# CFT-PB1-revG-TSSOP.net
KiCad netlist of a schematic drawn in EAGLE
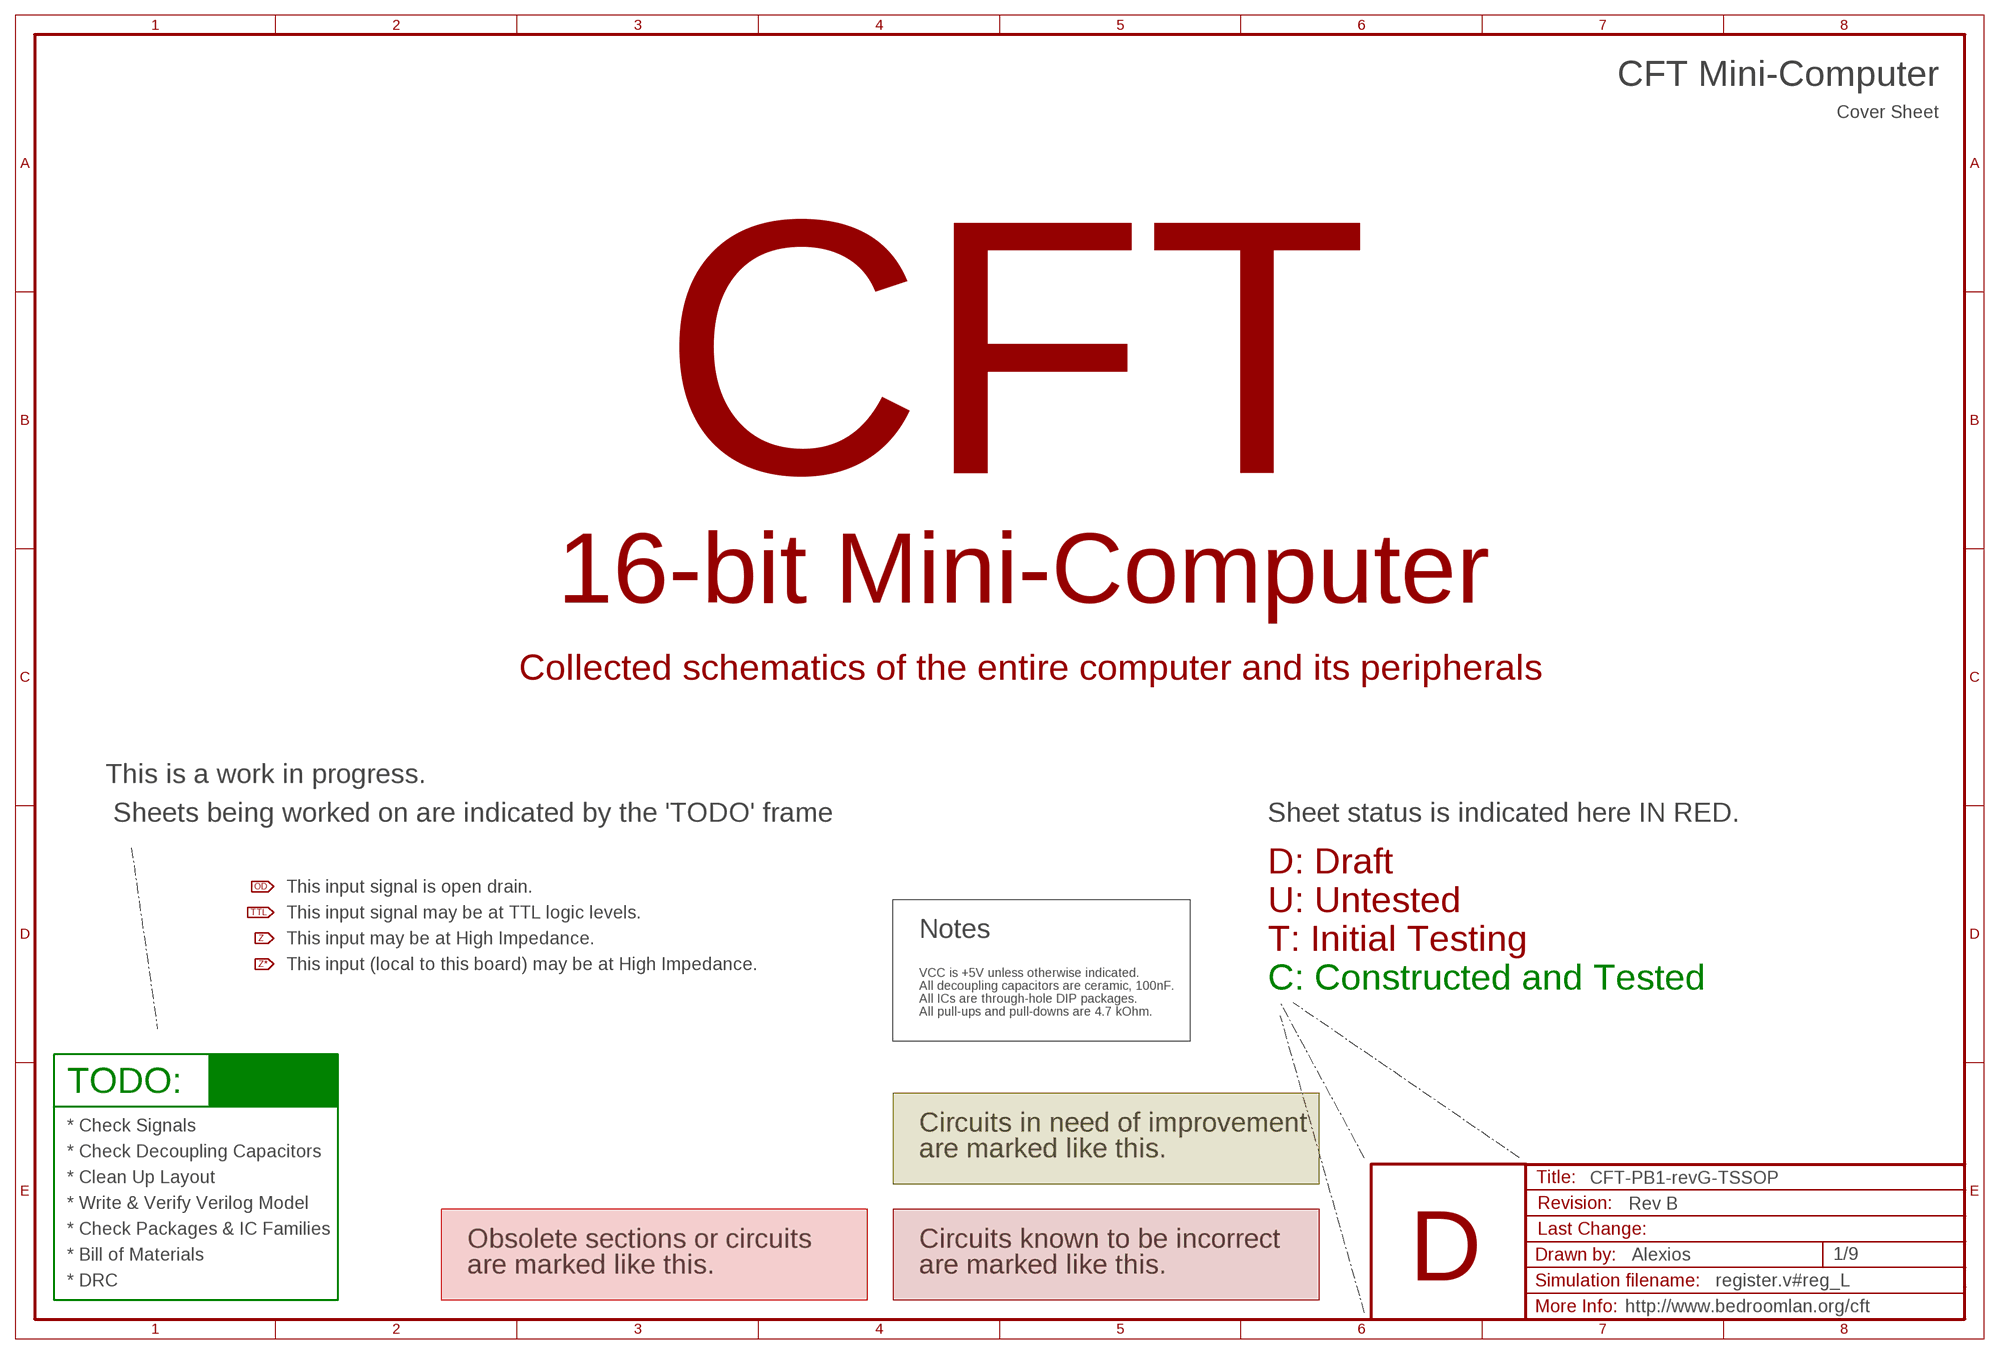
[diagram p0: schematic, sheet 1]
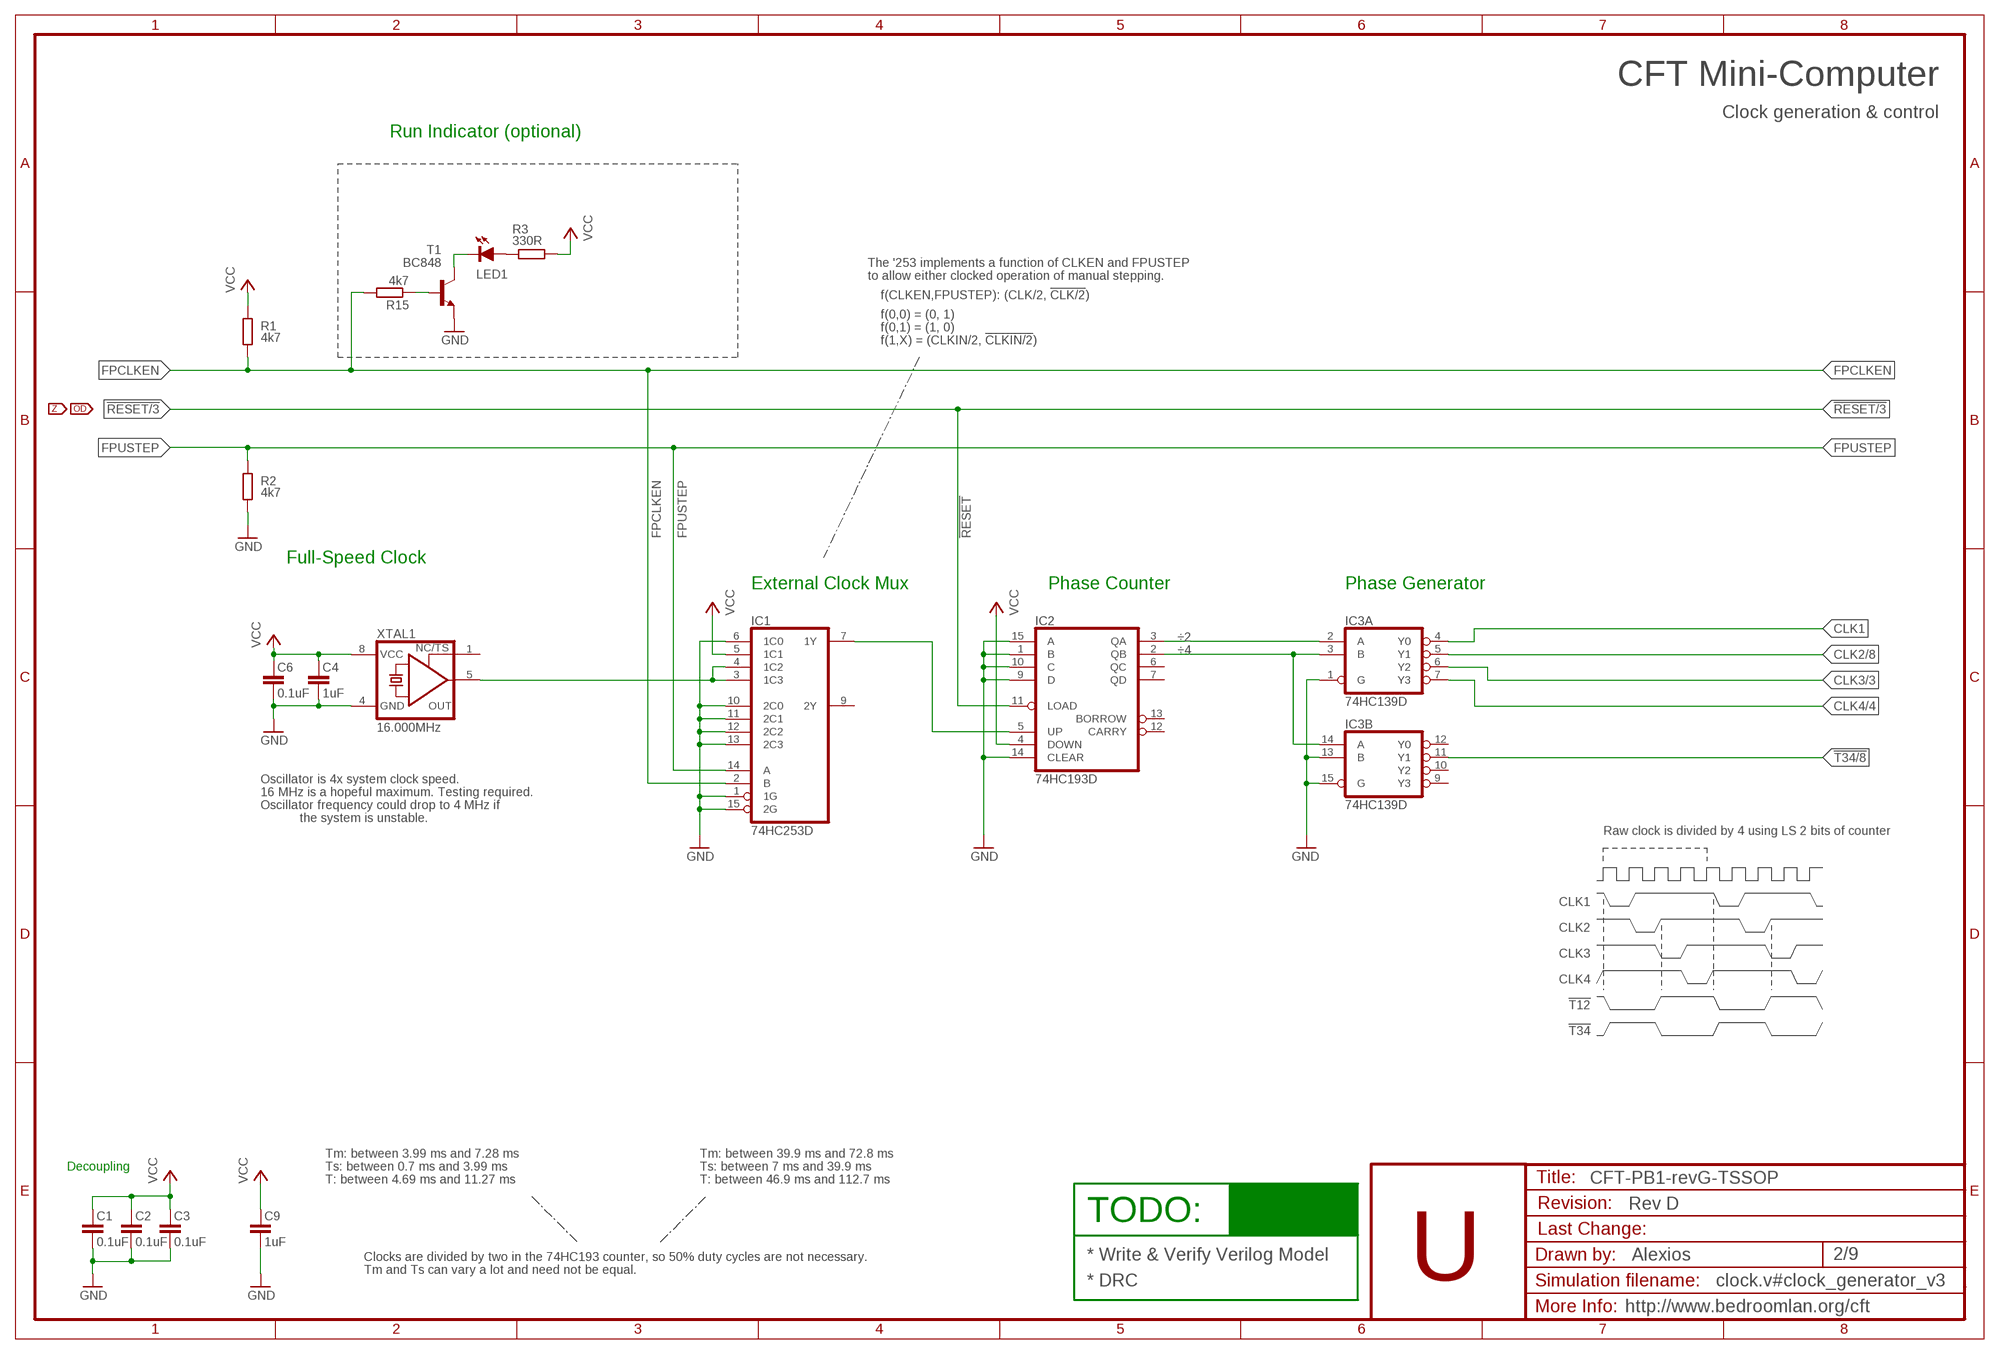
[diagram p1: schematic, sheet 2]
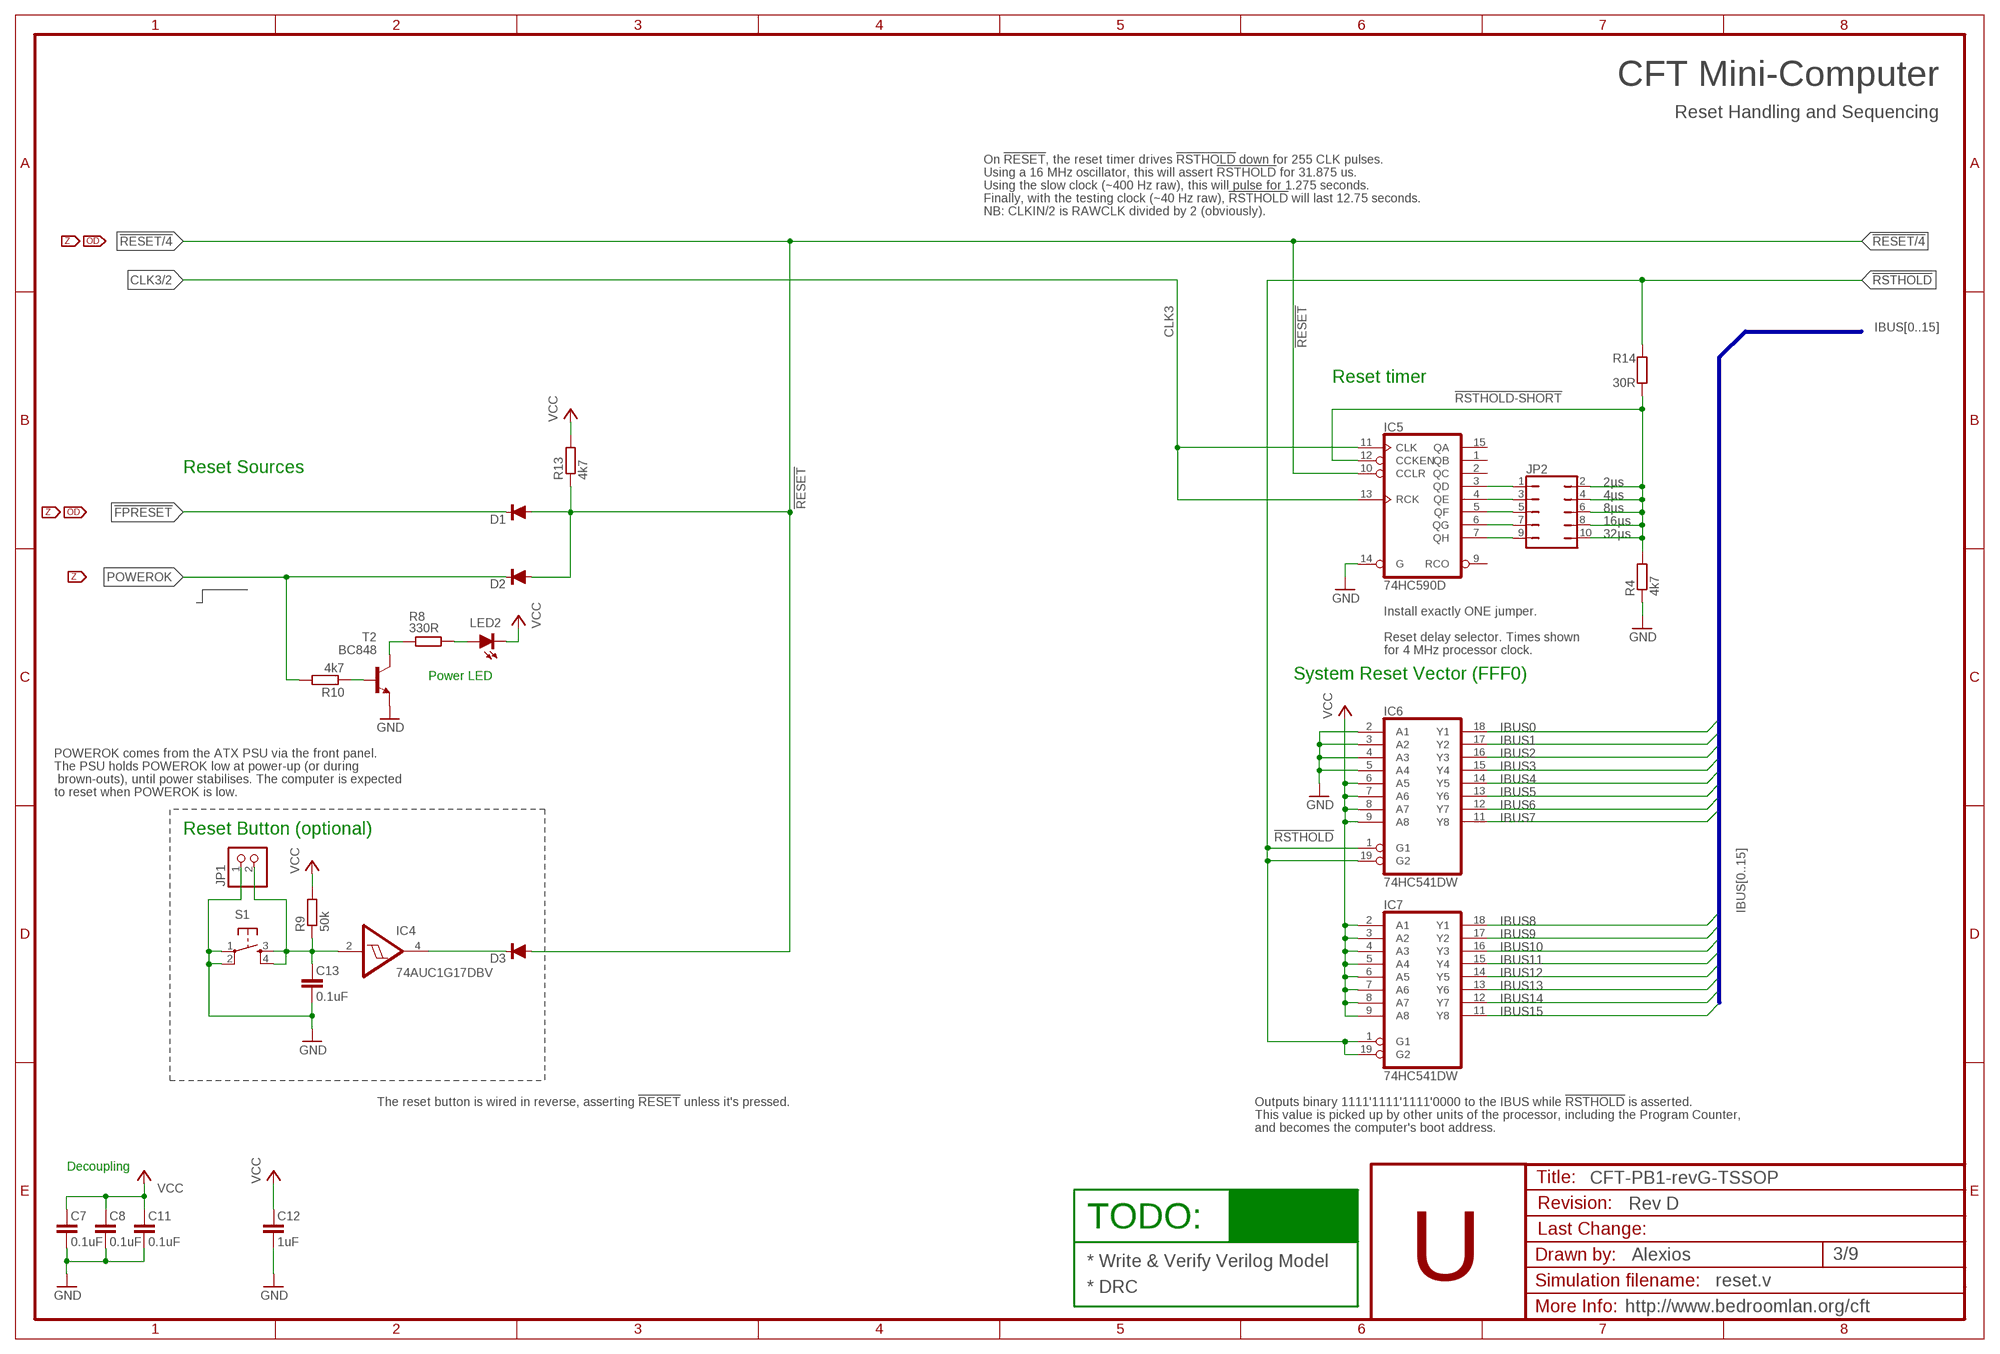
[diagram p2: schematic, sheet 3]
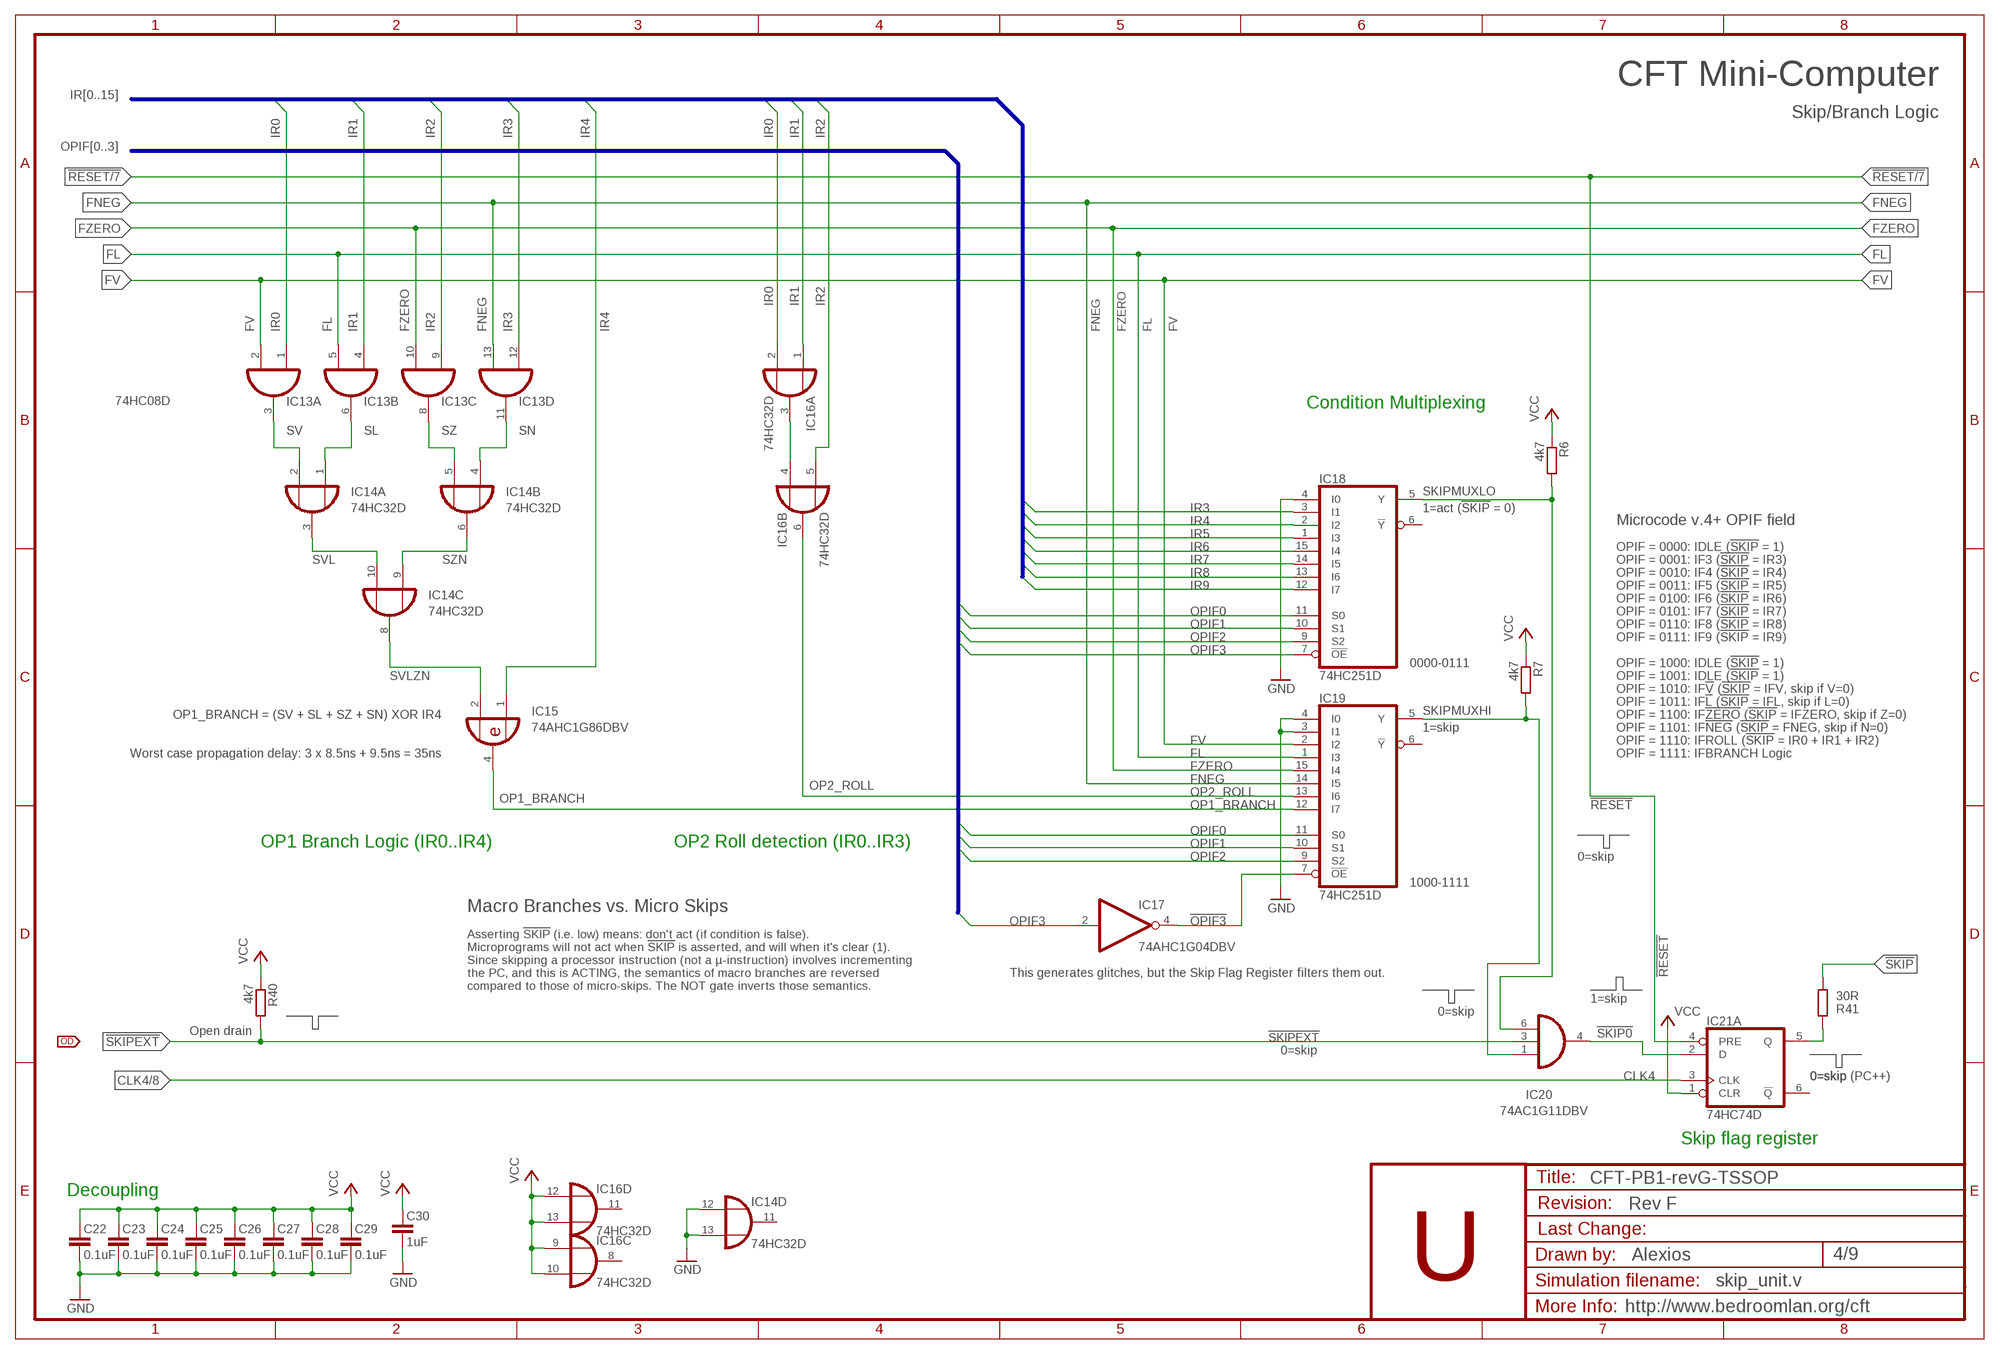
[diagram p3: schematic, sheet 4]
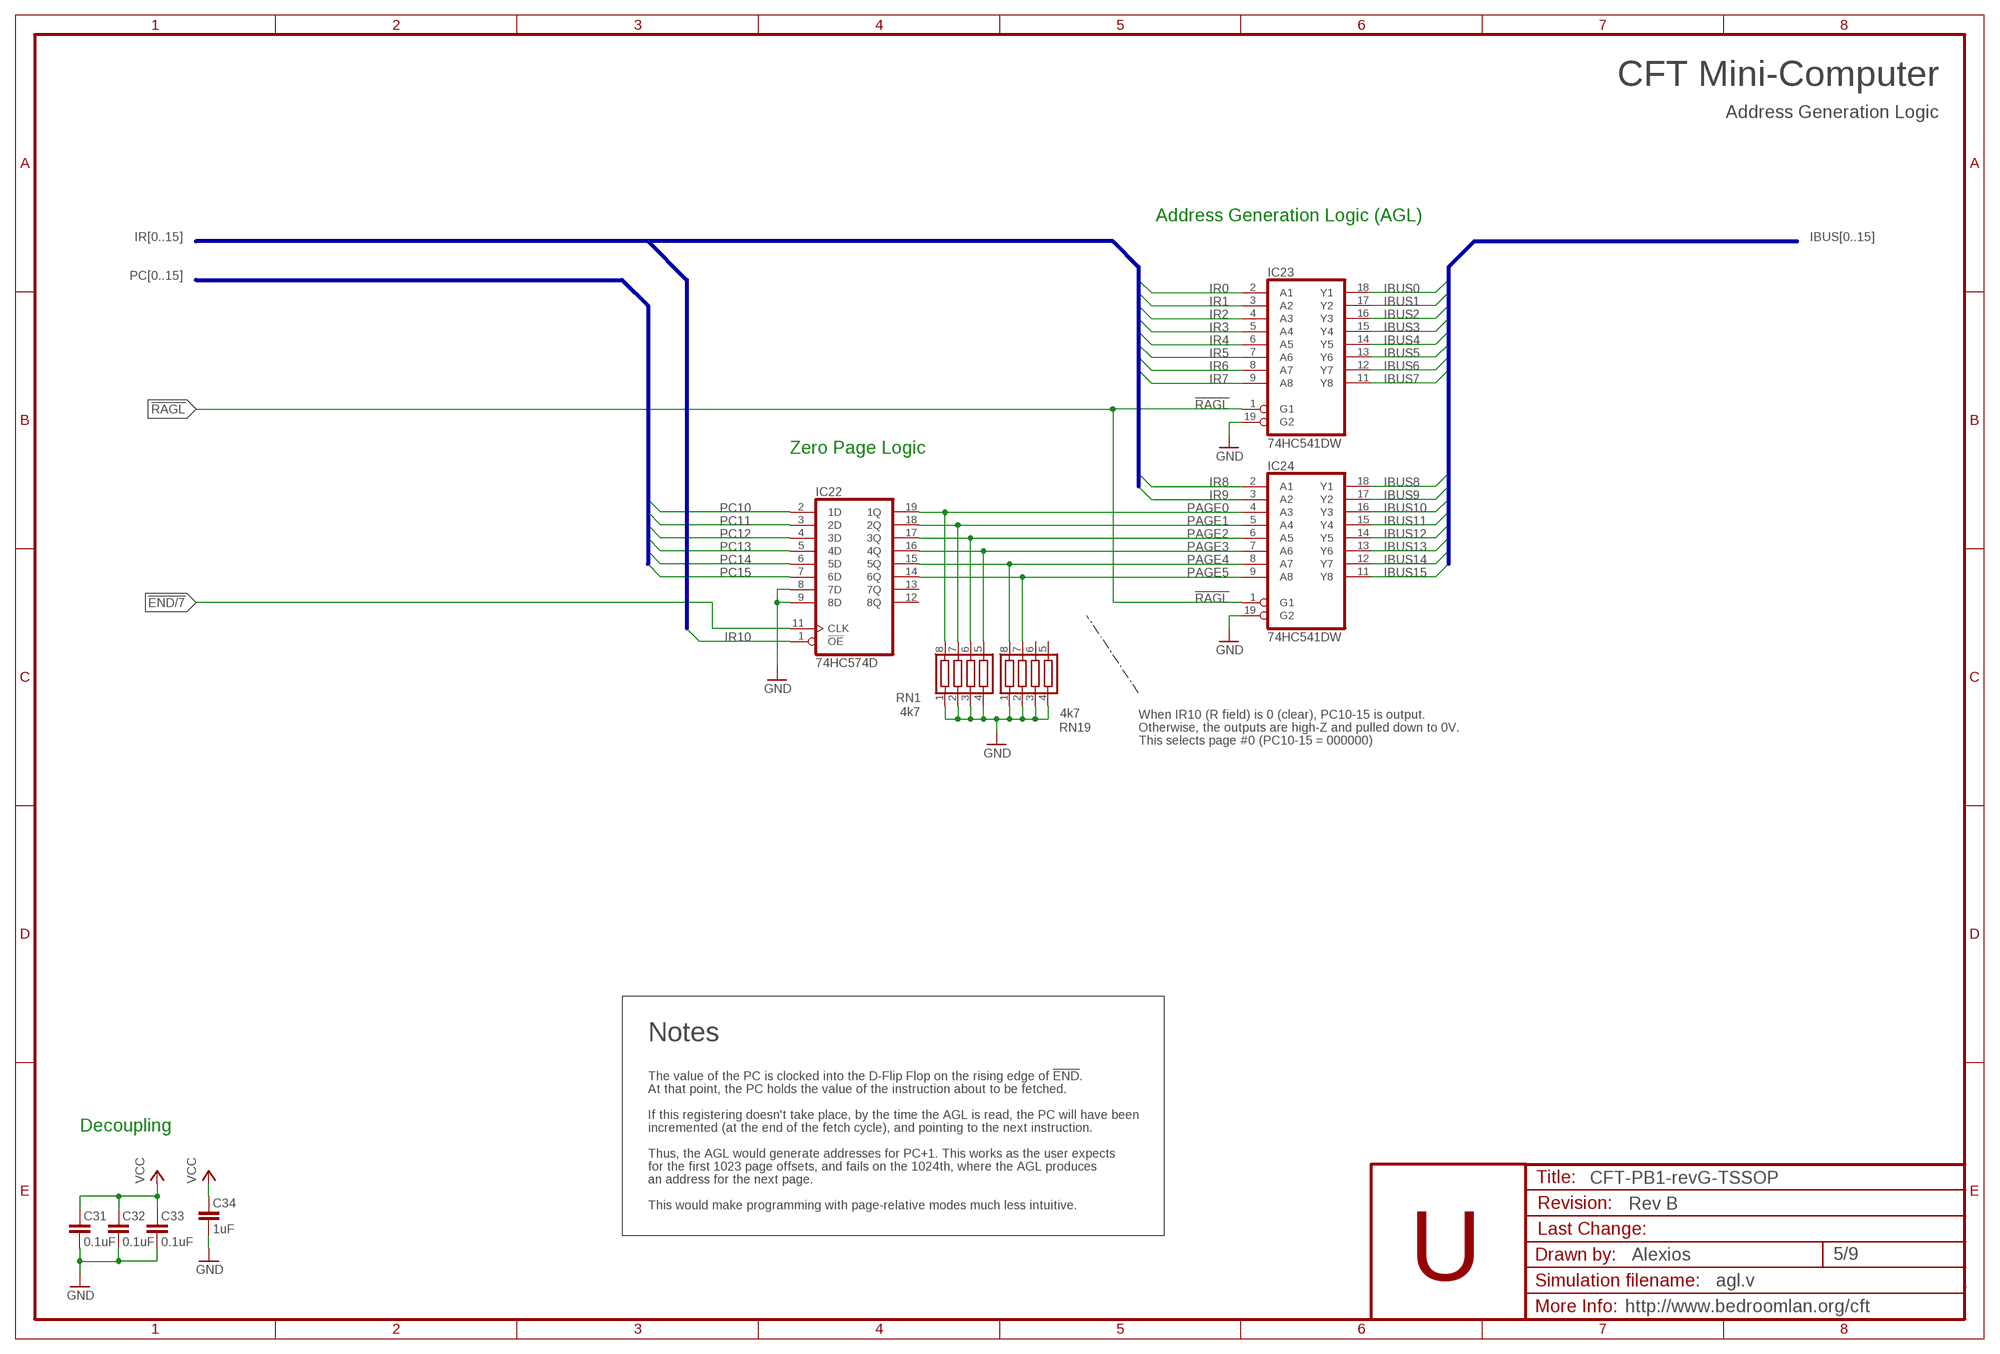
[diagram p4: schematic, sheet 5]
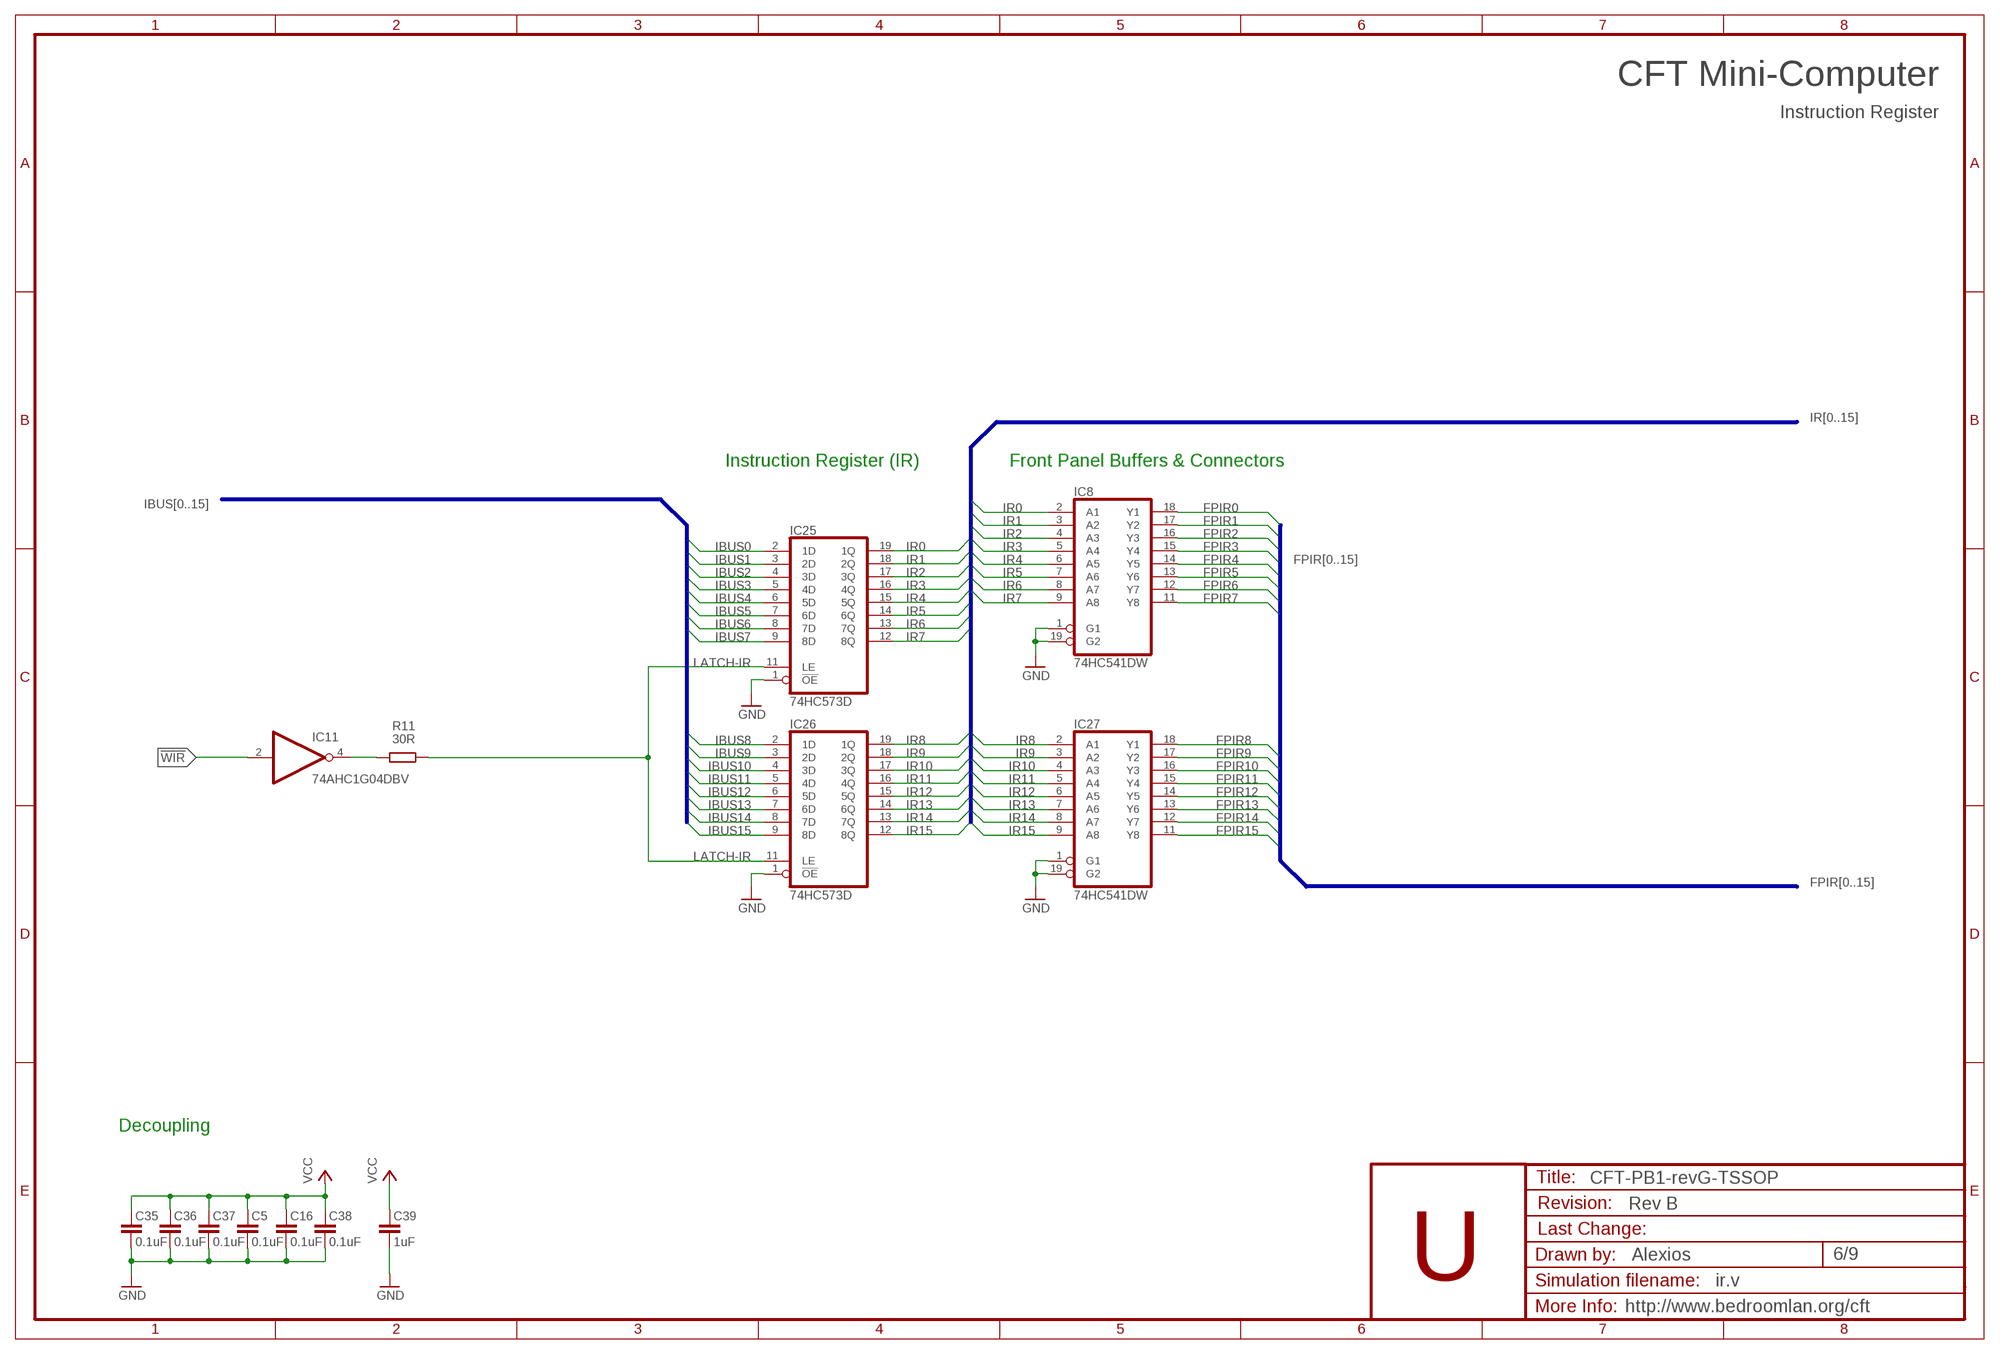
[diagram p5: schematic, sheet 6]
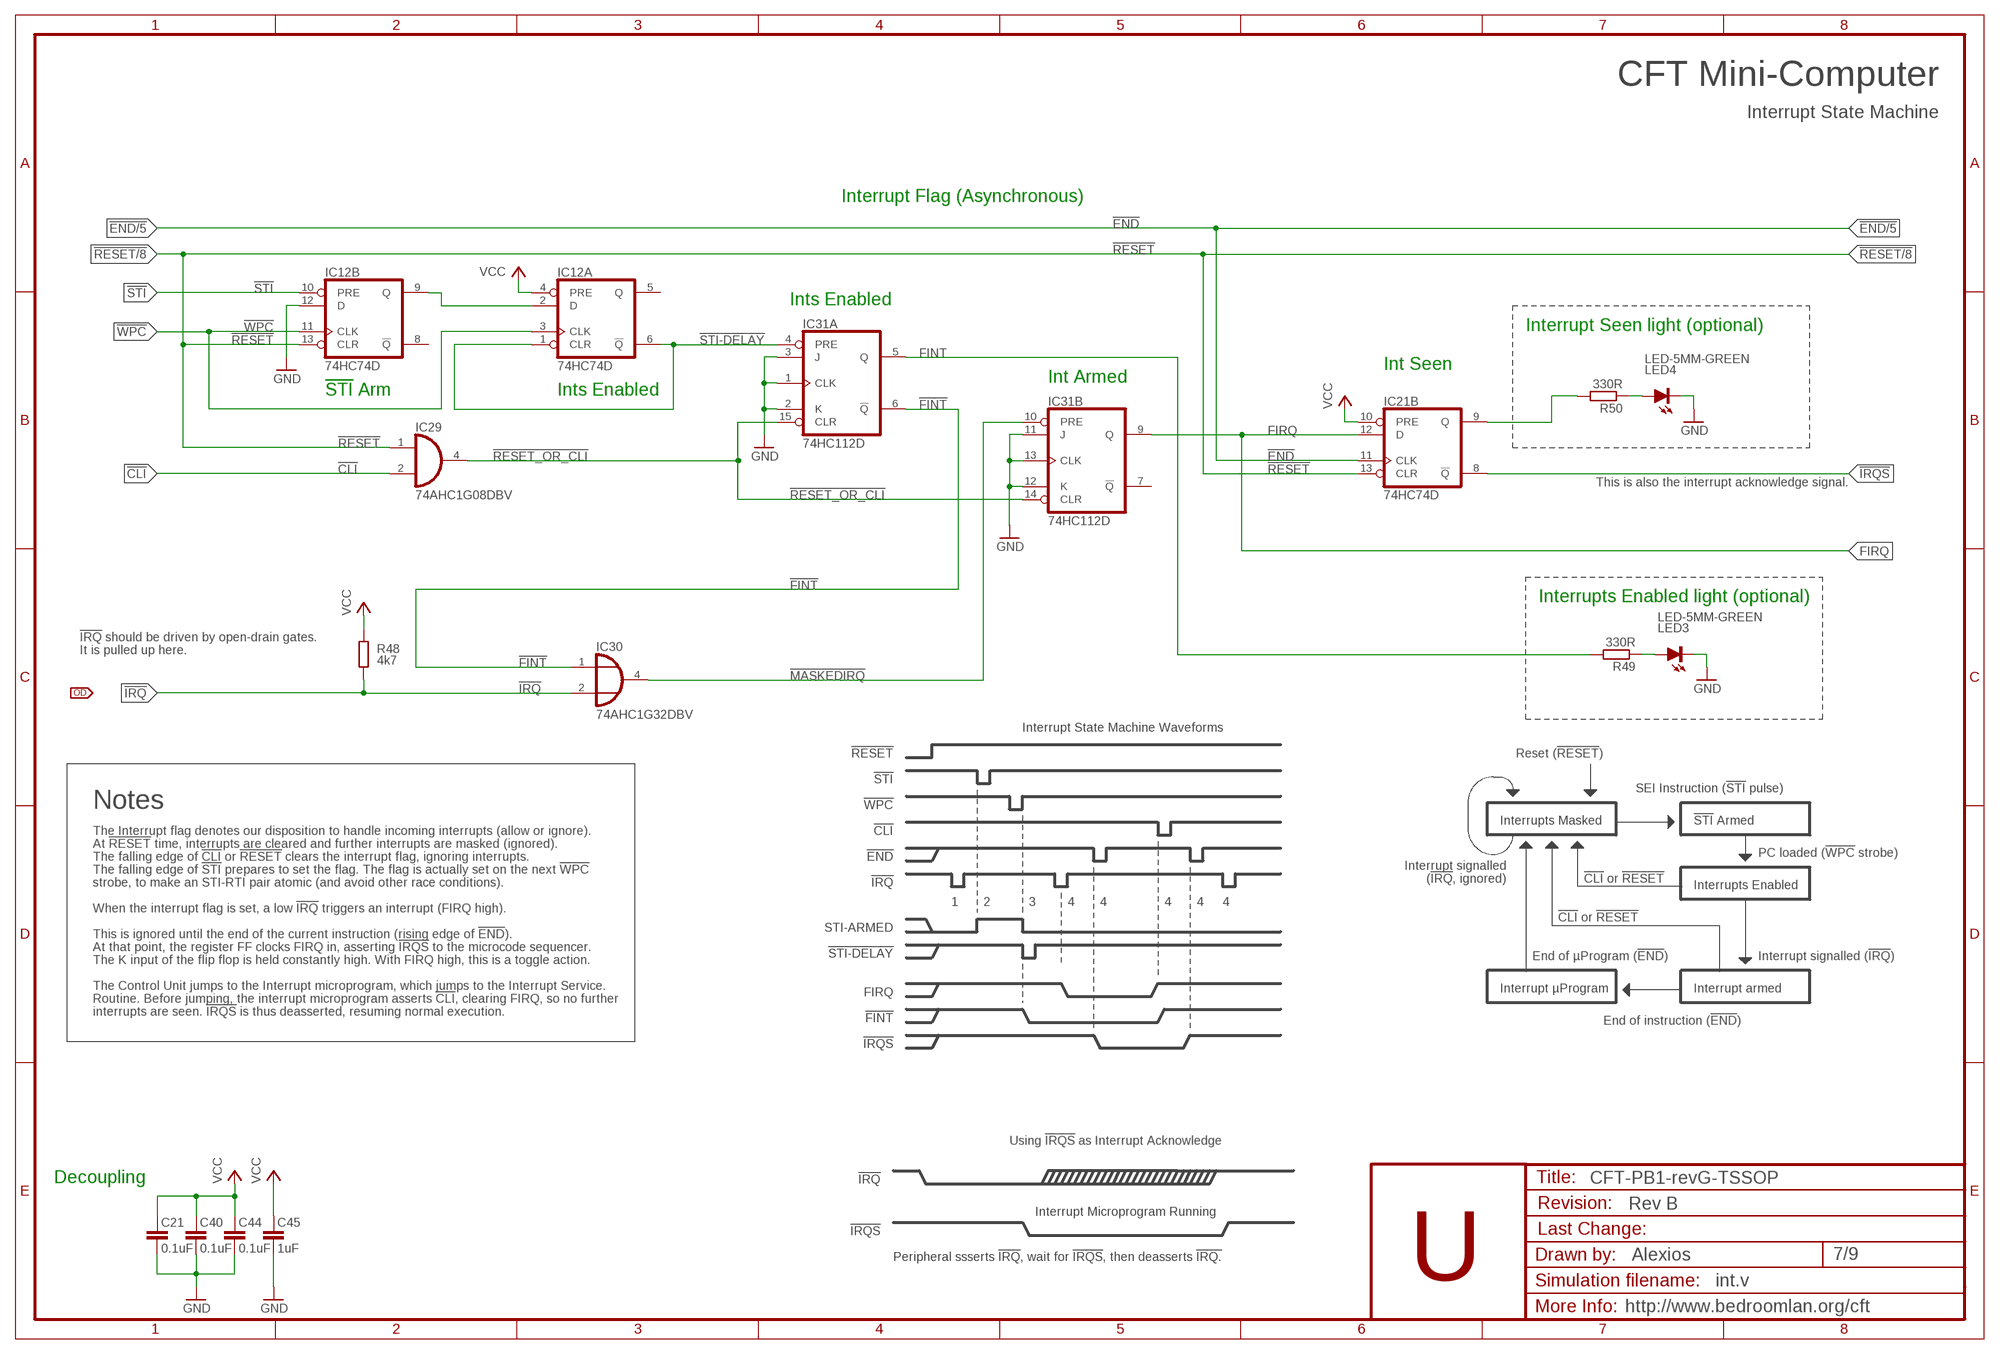
[diagram p6: schematic, sheet 7]
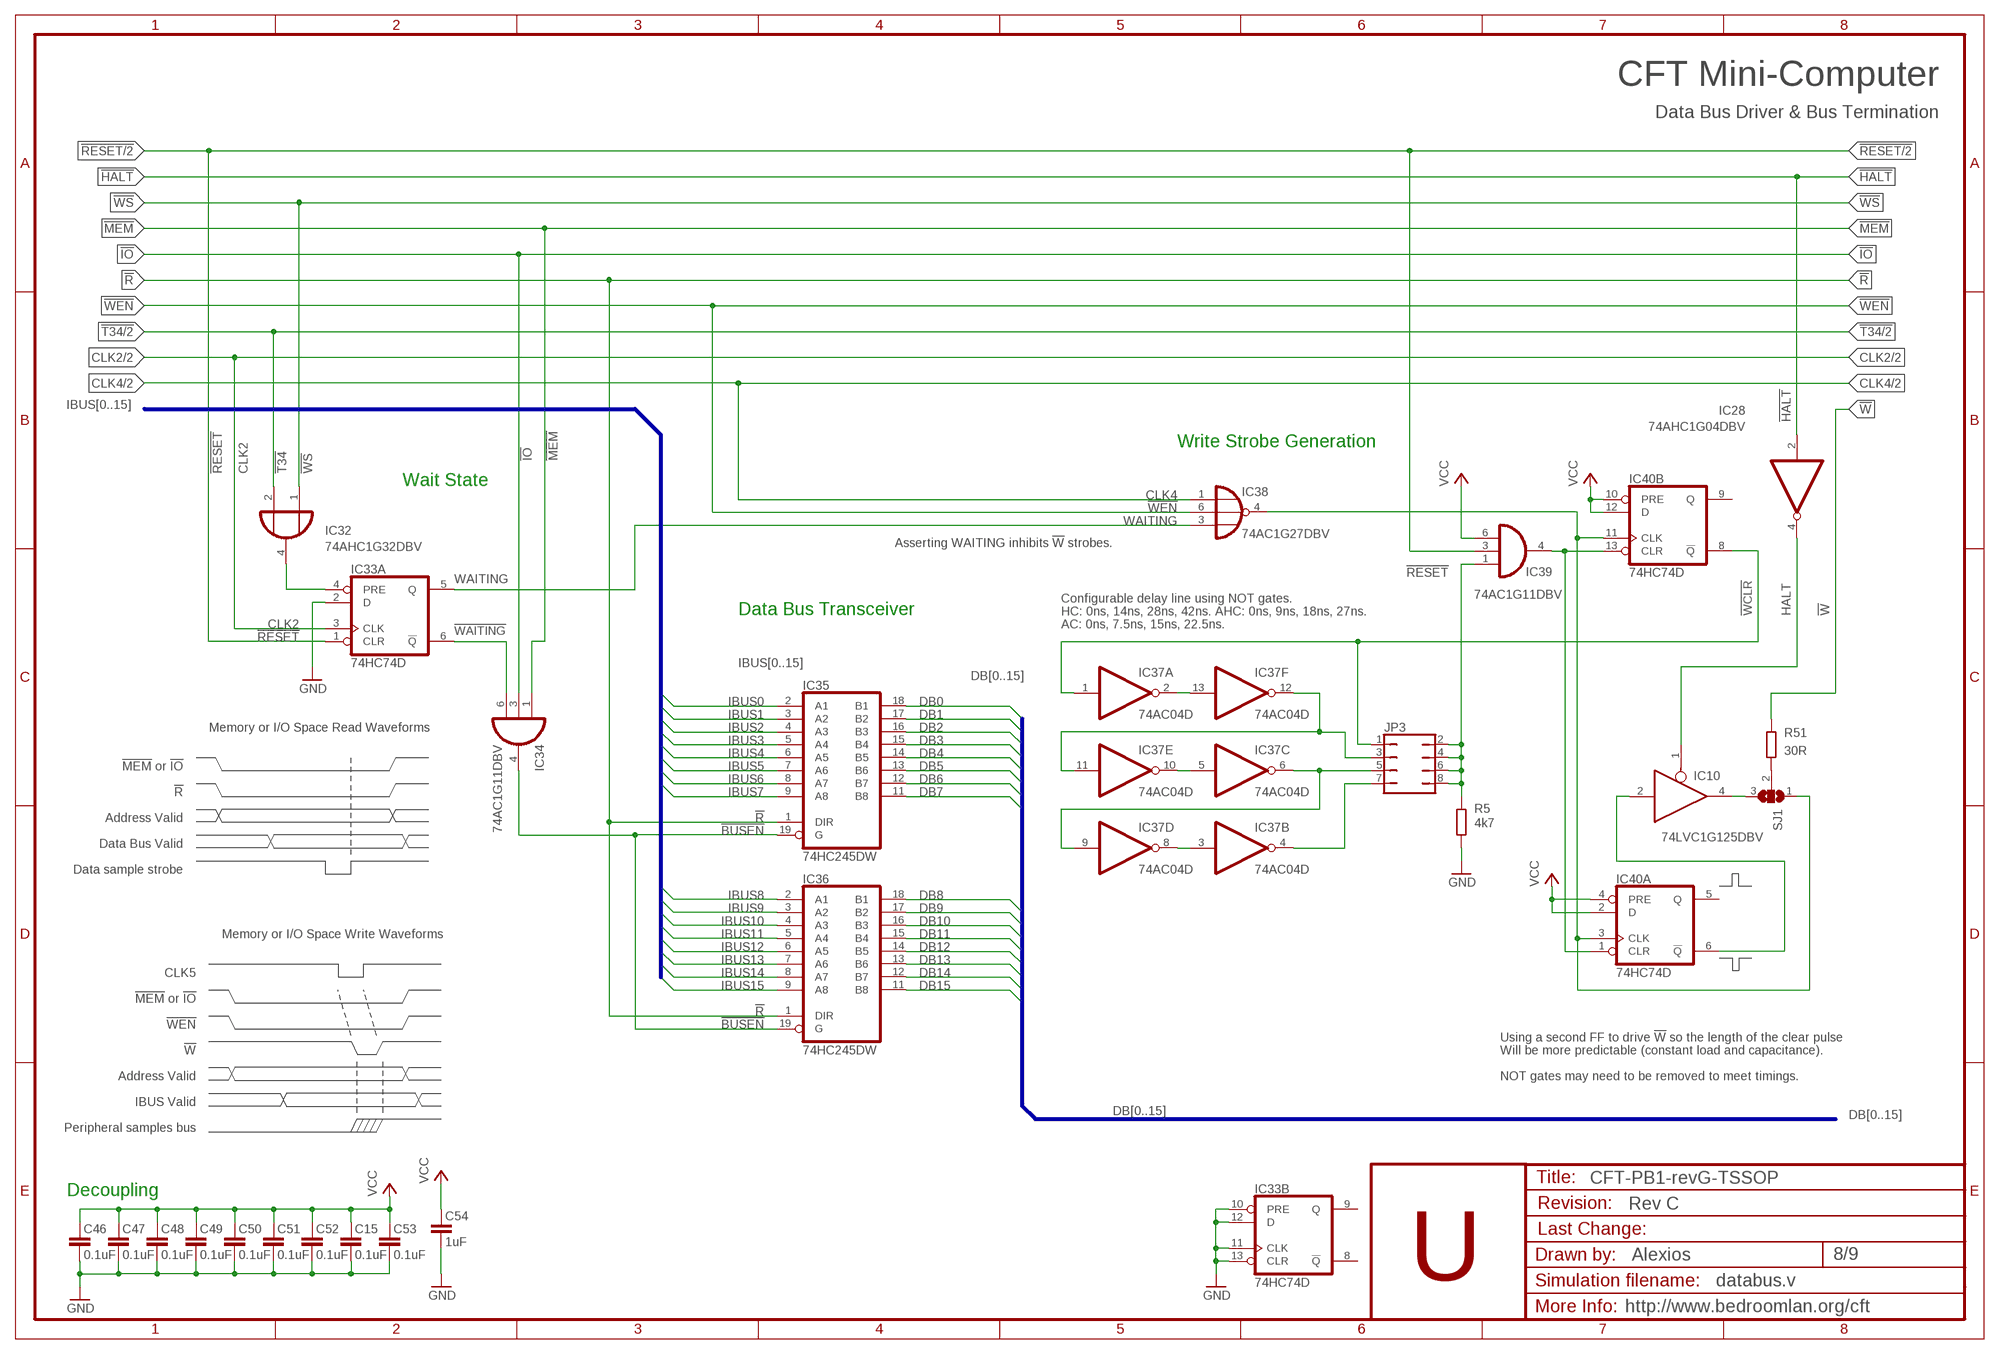
[diagram p7: schematic, sheet 8]
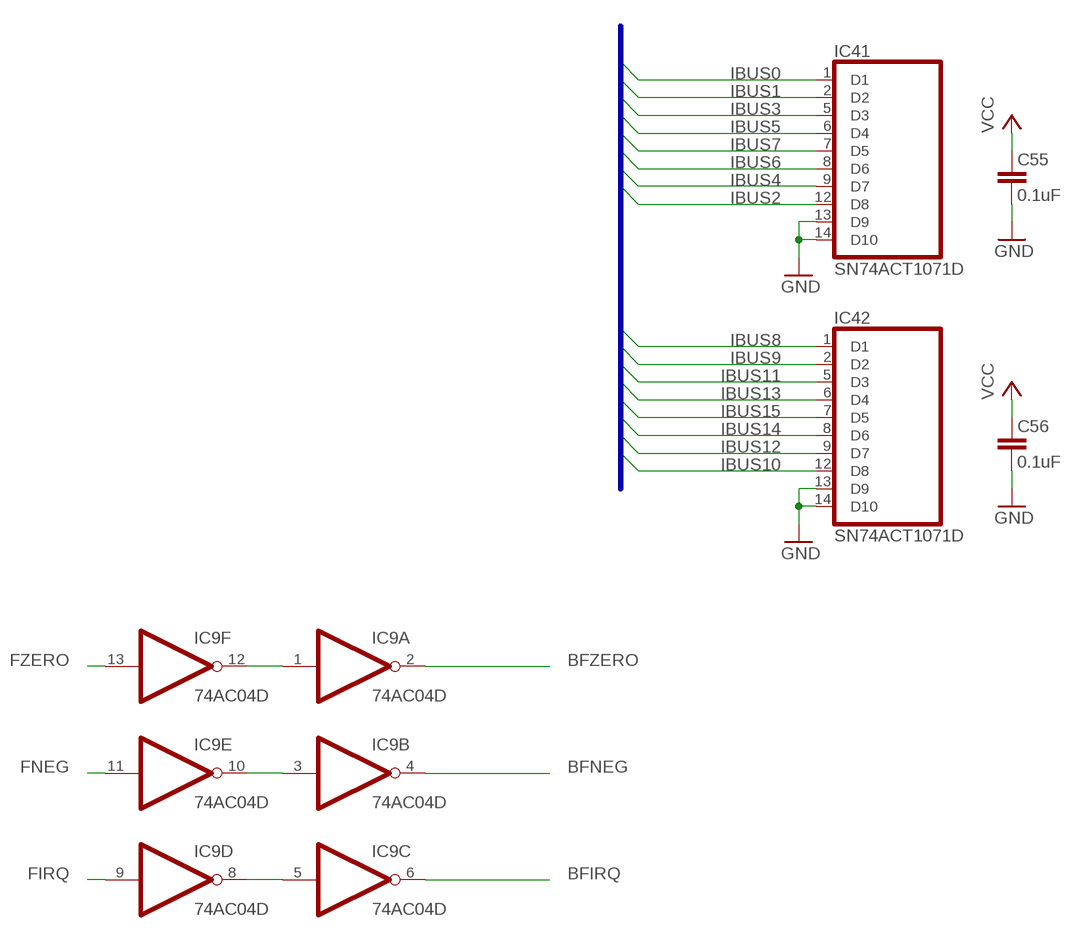
[diagram p8: schematic, sheet 9, part 1 of 2]
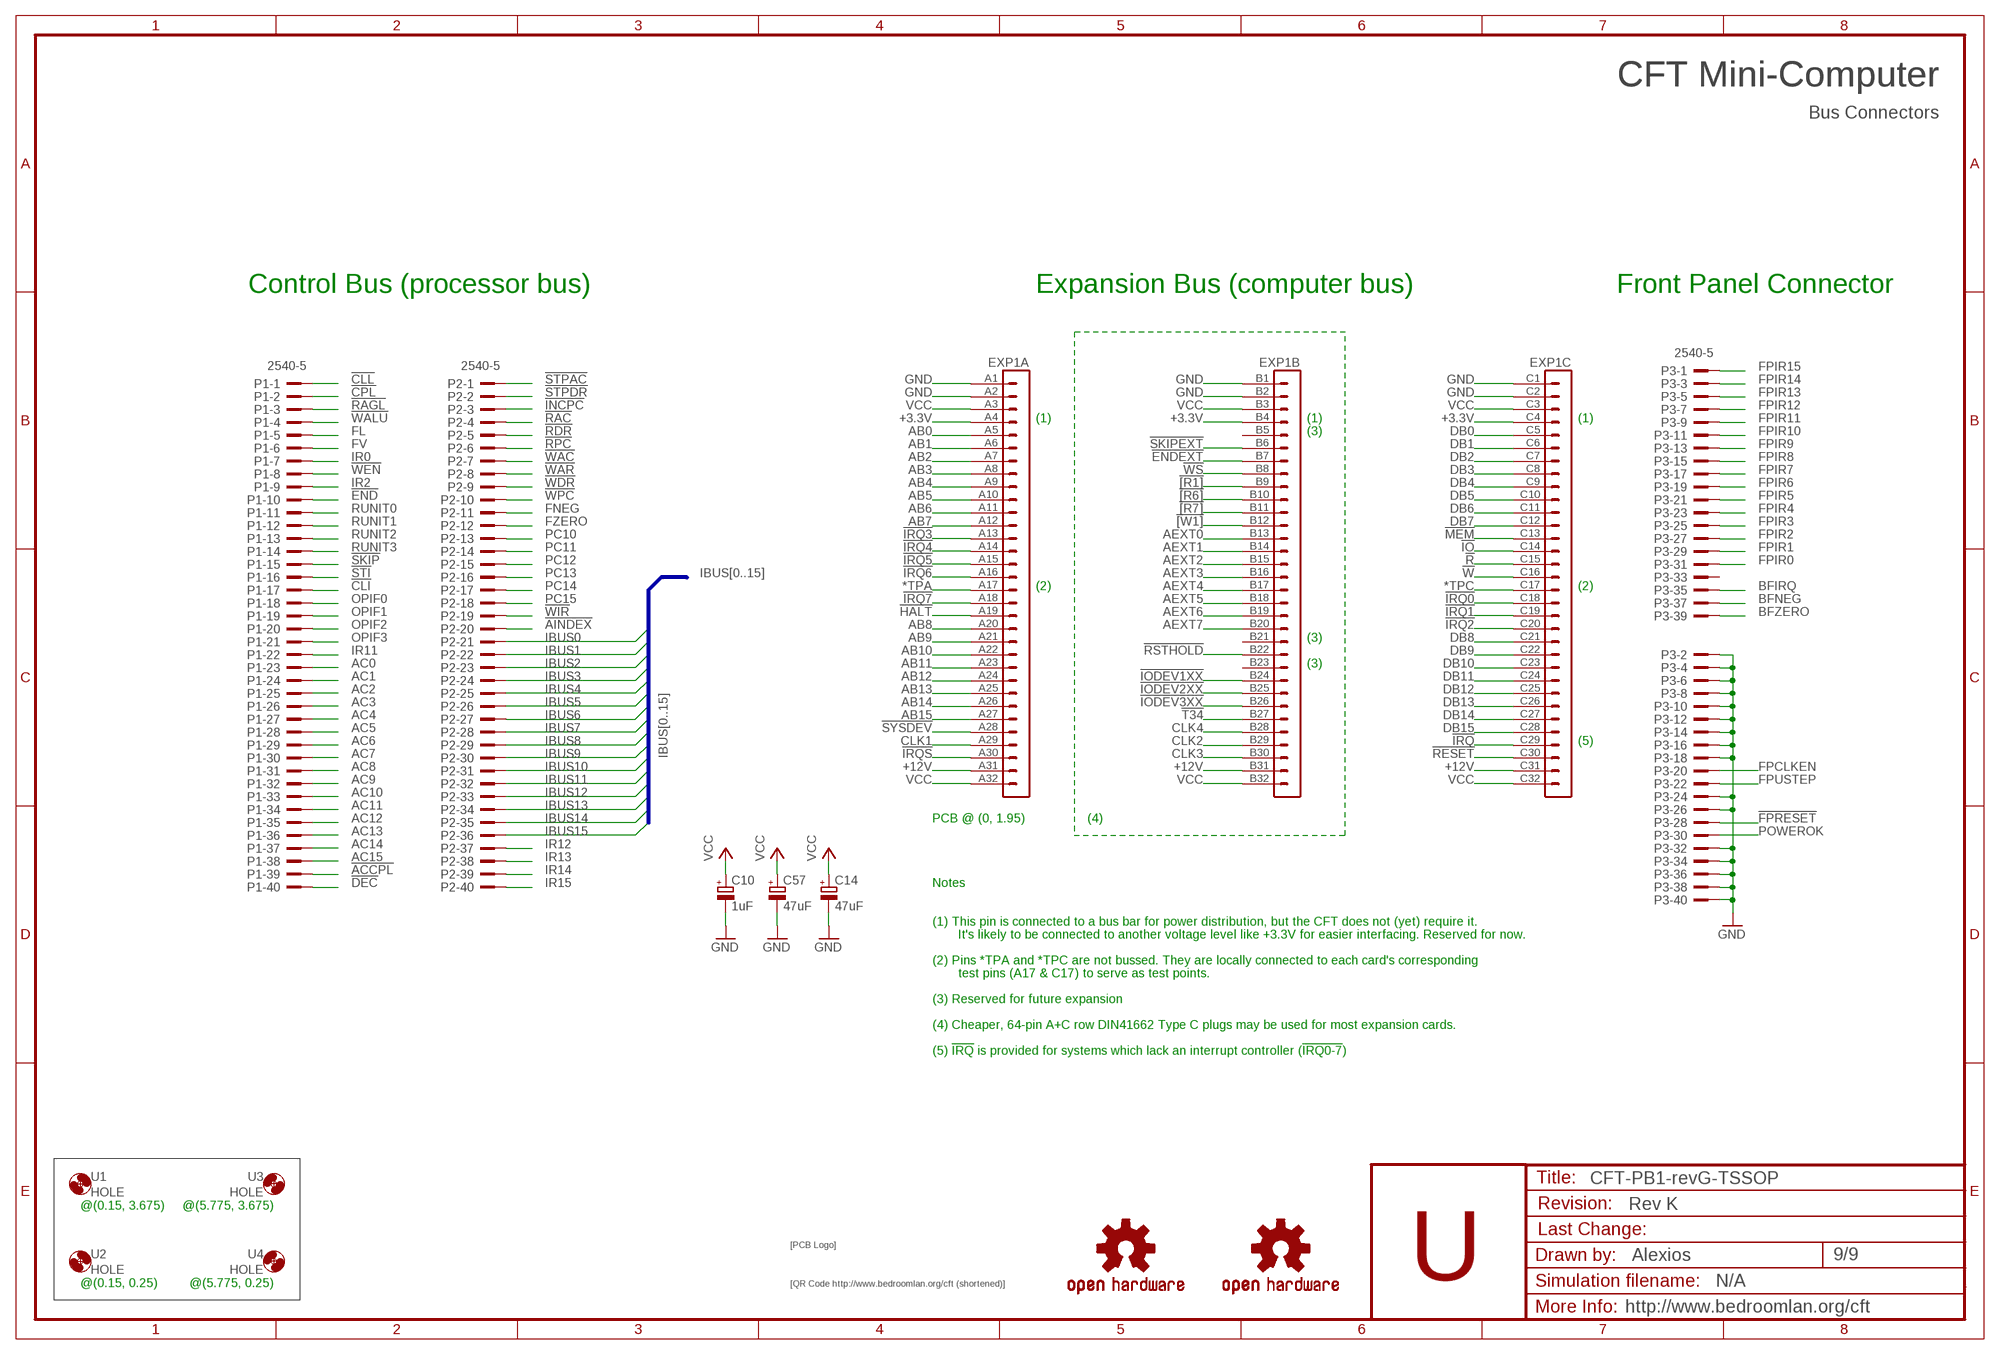
[diagram p9: schematic, sheet 9, part 2 of 2]

(export (version "E")
  (design (tool "Eeschema 10.0.6"))
  (components
    (comp (ref "C1")
      (value "0.1uF")
      (footprint "eagle-import:C0805K")
      (libsource (lib "eagle-import") (part "C-EUC0805K"))
    )
    (comp (ref "C2")
      (value "0.1uF")
      (footprint "eagle-import:C0805K")
      (libsource (lib "eagle-import") (part "C-EUC0805K"))
    )
    (comp (ref "C3")
      (value "0.1uF")
      (footprint "eagle-import:C0805K")
      (libsource (lib "eagle-import") (part "C-EUC0805K"))
    )
    (comp (ref "C4")
      (value "1uF")
      (footprint "eagle-import:C0805K")
      (libsource (lib "eagle-import") (part "C-EUC0805K"))
    )
    (comp (ref "C6")
      (value "0.1uF")
      (footprint "eagle-import:C0805K")
      (libsource (lib "eagle-import") (part "C-EUC0805K"))
    )
    (comp (ref "C9")
      (value "1uF")
      (footprint "eagle-import:C0805K")
      (libsource (lib "eagle-import") (part "C-EUC0805K"))
    )
    (comp (ref "IC1")
      (value "74HC253D")
      (footprint "eagle-import:SO16")
      (libsource (lib "eagle-import") (part "74253DHC"))
    )
    (comp (ref "IC2")
      (value "74HC193D")
      (footprint "eagle-import:SO16D")
      (libsource (lib "eagle-import") (part "74193DHC"))
    )
    (comp (ref "IC3")
      (value "74HC139D")
      (footprint "eagle-import:SO16")
      (libsource (lib "eagle-import") (part "74139DHC"))
    )
    (comp (ref "LED1")
      (value "LED-5MM-GREEN")
      (footprint "eagle-import:CHIPLED_0805")
      (libsource (lib "eagle-import") (part "LEDCHIPLED_0805"))
    )
    (comp (ref "R1")
      (value "4k7")
      (footprint "eagle-import:R0805")
      (libsource (lib "eagle-import") (part "resistor_R-EU_R0805"))
    )
    (comp (ref "R2")
      (value "4k7")
      (footprint "eagle-import:R0805")
      (libsource (lib "eagle-import") (part "resistor_R-EU_R0805"))
    )
    (comp (ref "R3")
      (value "330R")
      (footprint "eagle-import:R0805")
      (libsource (lib "eagle-import") (part "resistor_R-EU_R0805"))
    )
    (comp (ref "R15")
      (value "4k7")
      (footprint "eagle-import:R0805")
      (libsource (lib "eagle-import") (part "resistor_R-EU_R0805"))
    )
    (comp (ref "T1")
      (value "BC848")
      (footprint "eagle-import:SOT23")
      (libsource (lib "eagle-import") (part "BC848"))
    )
    (comp (ref "XTAL1")
      (value "16.000MHz")
      (footprint "eagle-import:DIL08S-SOCKET")
      (libsource (lib "eagle-import") (part "XO-08-SOCKET"))
    )
    (comp (ref "$4_37_$1")
      (value "SIGNATURESILK")
      (footprint "eagle-import:SIGNATURE")
      (libsource (lib "eagle-import") (part "SIGNATURESILK"))
    )
    (comp (ref "$4_39_$")
      (value "OSHW-LOGOL")
      (footprint "eagle-import:OSHW-LOGO-L")
      (libsource (lib "eagle-import") (part "OSHW-LOGOL"))
    )
    (comp (ref "$4_39_$1")
      (value "OSHW-LOGOL")
      (footprint "eagle-import:OSHW-LOGO-L")
      (libsource (lib "eagle-import") (part "OSHW-LOGOL"))
    )
    (comp (ref "$4_40_$")
      (value "QRCODE-CFT")
      (footprint "eagle-import:CFT-QRCODE")
      (libsource (lib "eagle-import") (part "QRCODE-CFT"))
    )
    (comp (ref "C10")
      (value "1uF")
      (footprint "eagle-import:E2,5-5")
      (libsource (lib "eagle-import") (part "CPOL-EUE2.5-5"))
    )
    (comp (ref "C14")
      (value "47uF")
      (footprint "eagle-import:E2,5-5")
      (libsource (lib "eagle-import") (part "CPOL-EUE2.5-5"))
    )
    (comp (ref "C55")
      (value "0.1uF")
      (footprint "eagle-import:C0805K")
      (libsource (lib "eagle-import") (part "C-EUC0805K"))
    )
    (comp (ref "C56")
      (value "0.1uF")
      (footprint "eagle-import:C0805K")
      (libsource (lib "eagle-import") (part "C-EUC0805K"))
    )
    (comp (ref "C57")
      (value "47uF")
      (footprint "eagle-import:E2,5-5")
      (libsource (lib "eagle-import") (part "CPOL-EUE2.5-5"))
    )
    (comp (ref "EXP1")
      (value "VG96-3K")
      (footprint "eagle-import:VG96K")
      (libsource (lib "eagle-import") (part "VG96-3K"))
    )
    (comp (ref "IC9")
      (value "74AC04D")
      (footprint "eagle-import:SO14")
      (libsource (lib "eagle-import") (part "7404DAC"))
    )
    (comp (ref "IC41")
      (value "SN74ACT1071D")
      (footprint "eagle-import:SO14")
      (libsource (lib "eagle-import") (part "SN74ACT1071D"))
    )
    (comp (ref "IC42")
      (value "SN74ACT1071D")
      (footprint "eagle-import:SO14")
      (libsource (lib "eagle-import") (part "SN74ACT1071D"))
    )
    (comp (ref "P1")
      (value "2540-5")
      (footprint "eagle-import:PAK100_2500-5-40")
      (libsource (lib "eagle-import") (part "2540-5"))
    )
    (comp (ref "P2")
      (value "2540-5")
      (footprint "eagle-import:PAK100_2500-5-40")
      (libsource (lib "eagle-import") (part "2540-5"))
    )
    (comp (ref "P3")
      (value "2540-5")
      (footprint "eagle-import:PAK100_2500-5-40")
      (libsource (lib "eagle-import") (part "2540-5"))
    )
    (comp (ref "U1")
      (value "HOLE")
      (footprint "eagle-import:STANDOFF_28_60")
      (libsource (lib "eagle-import") (part "HOLE"))
    )
    (comp (ref "U2")
      (value "HOLE")
      (footprint "eagle-import:STANDOFF_28_60")
      (libsource (lib "eagle-import") (part "HOLE"))
    )
    (comp (ref "U3")
      (value "HOLE")
      (footprint "eagle-import:STANDOFF_28_60")
      (libsource (lib "eagle-import") (part "HOLE"))
    )
    (comp (ref "U4")
      (value "HOLE")
      (footprint "eagle-import:STANDOFF_28_60")
      (libsource (lib "eagle-import") (part "HOLE"))
    )
    (comp (ref "C15")
      (value "0.1uF")
      (footprint "eagle-import:C0805K")
      (libsource (lib "eagle-import") (part "C-EUC0805K"))
    )
    (comp (ref "C46")
      (value "0.1uF")
      (footprint "eagle-import:C0805K")
      (libsource (lib "eagle-import") (part "C-EUC0805K"))
    )
    (comp (ref "C47")
      (value "0.1uF")
      (footprint "eagle-import:C0805K")
      (libsource (lib "eagle-import") (part "C-EUC0805K"))
    )
    (comp (ref "C48")
      (value "0.1uF")
      (footprint "eagle-import:C0805K")
      (libsource (lib "eagle-import") (part "C-EUC0805K"))
    )
    (comp (ref "C49")
      (value "0.1uF")
      (footprint "eagle-import:C0805K")
      (libsource (lib "eagle-import") (part "C-EUC0805K"))
    )
    (comp (ref "C50")
      (value "0.1uF")
      (footprint "eagle-import:C0805K")
      (libsource (lib "eagle-import") (part "C-EUC0805K"))
    )
    (comp (ref "C51")
      (value "0.1uF")
      (footprint "eagle-import:C0805K")
      (libsource (lib "eagle-import") (part "C-EUC0805K"))
    )
    (comp (ref "C52")
      (value "0.1uF")
      (footprint "eagle-import:C0805K")
      (libsource (lib "eagle-import") (part "C-EUC0805K"))
    )
    (comp (ref "C53")
      (value "0.1uF")
      (footprint "eagle-import:C0805K")
      (libsource (lib "eagle-import") (part "C-EUC0805K"))
    )
    (comp (ref "C54")
      (value "1uF")
      (footprint "eagle-import:C0805K")
      (libsource (lib "eagle-import") (part "C-EUC0805K"))
    )
    (comp (ref "IC10")
      (value "74LVC1G125DBV")
      (footprint "eagle-import:SOT23-5")
      (libsource (lib "eagle-import") (part "741G125DBVLVC"))
    )
    (comp (ref "IC28")
      (value "74AHC1G04DBV")
      (footprint "eagle-import:SOT23-5")
      (libsource (lib "eagle-import") (part "741G04DBVAHC"))
    )
    (comp (ref "IC32")
      (value "74AHC1G32DBV")
      (footprint "eagle-import:SOT23-5")
      (libsource (lib "eagle-import") (part "741G32DBVAHC"))
    )
    (comp (ref "IC33")
      (value "74HC74D")
      (footprint "eagle-import:SO14")
      (libsource (lib "eagle-import") (part "7474DHC"))
    )
    (comp (ref "IC34")
      (value "74AC1G11DBV")
      (footprint "eagle-import:DBV_R-PDSO-G6")
      (libsource (lib "eagle-import") (part "741G11DBVAC"))
    )
    (comp (ref "IC35")
      (value "74HC245DW")
      (footprint "eagle-import:SO20W")
      (libsource (lib "eagle-import") (part "74245DWHC"))
    )
    (comp (ref "IC36")
      (value "74HC245DW")
      (footprint "eagle-import:SO20W")
      (libsource (lib "eagle-import") (part "74245DWHC"))
    )
    (comp (ref "IC37")
      (value "74AC04D")
      (footprint "eagle-import:SO14")
      (libsource (lib "eagle-import") (part "7404DAC"))
    )
    (comp (ref "IC38")
      (value "74AC1G27DBV")
      (footprint "eagle-import:DBV_R-PDSO-G6")
      (libsource (lib "eagle-import") (part "741G27DBVAC"))
    )
    (comp (ref "IC39")
      (value "74AC1G11DBV")
      (footprint "eagle-import:DBV_R-PDSO-G6")
      (libsource (lib "eagle-import") (part "741G11DBVAC"))
    )
    (comp (ref "IC40")
      (value "74HC74D")
      (footprint "eagle-import:SO14")
      (libsource (lib "eagle-import") (part "7474DHC"))
    )
    (comp (ref "JP3")
      (value "JP4Q")
      (footprint "eagle-import:JP4Q")
      (libsource (lib "eagle-import") (part "JP4Q"))
    )
    (comp (ref "R5")
      (value "4k7")
      (footprint "eagle-import:R0805")
      (libsource (lib "eagle-import") (part "resistor_R-EU_R0805"))
    )
    (comp (ref "R51")
      (value "30R")
      (footprint "eagle-import:R0805")
      (libsource (lib "eagle-import") (part "resistor_R-EU_R0805"))
    )
    (comp (ref "SJ1")
      (value "SJ2W")
      (footprint "eagle-import:SJ_2")
      (libsource (lib "eagle-import") (part "SJ2W"))
    )
    (comp (ref "C31")
      (value "0.1uF")
      (footprint "eagle-import:C0805K")
      (libsource (lib "eagle-import") (part "C-EUC0805K"))
    )
    (comp (ref "C32")
      (value "0.1uF")
      (footprint "eagle-import:C0805K")
      (libsource (lib "eagle-import") (part "C-EUC0805K"))
    )
    (comp (ref "C33")
      (value "0.1uF")
      (footprint "eagle-import:C0805K")
      (libsource (lib "eagle-import") (part "C-EUC0805K"))
    )
    (comp (ref "C34")
      (value "1uF")
      (footprint "eagle-import:C0805K")
      (libsource (lib "eagle-import") (part "C-EUC0805K"))
    )
    (comp (ref "IC22")
      (value "74HC574D")
      (footprint "eagle-import:SO20W")
      (libsource (lib "eagle-import") (part "74574DHC"))
    )
    (comp (ref "IC23")
      (value "74HC541DW")
      (footprint "eagle-import:SO20W")
      (libsource (lib "eagle-import") (part "74541DWHC"))
    )
    (comp (ref "IC24")
      (value "74HC541DW")
      (footprint "eagle-import:SO20W")
      (libsource (lib "eagle-import") (part "74541DWHC"))
    )
    (comp (ref "RN1")
      (value "4k7")
      (footprint "eagle-import:CTS742C083")
      (libsource (lib "eagle-import") (part "CTS742C083"))
    )
    (comp (ref "RN19")
      (value "4k7")
      (footprint "eagle-import:CTS742C083")
      (libsource (lib "eagle-import") (part "CTS742C083"))
    )
    (comp (ref "C7")
      (value "0.1uF")
      (footprint "eagle-import:C0805K")
      (libsource (lib "eagle-import") (part "C-EUC0805K"))
    )
    (comp (ref "C8")
      (value "0.1uF")
      (footprint "eagle-import:C0805K")
      (libsource (lib "eagle-import") (part "C-EUC0805K"))
    )
    (comp (ref "C11")
      (value "0.1uF")
      (footprint "eagle-import:C0805K")
      (libsource (lib "eagle-import") (part "C-EUC0805K"))
    )
    (comp (ref "C12")
      (value "1uF")
      (footprint "eagle-import:C0805K")
      (libsource (lib "eagle-import") (part "C-EUC0805K"))
    )
    (comp (ref "C13")
      (value "0.1uF")
      (footprint "eagle-import:C0805K")
      (libsource (lib "eagle-import") (part "C-EUC0805K"))
    )
    (comp (ref "D1")
      (value "DIODE-SOD123")
      (footprint "eagle-import:SOD123")
      (libsource (lib "eagle-import") (part "DIODE-SOD123"))
    )
    (comp (ref "D2")
      (value "DIODE-SOD123")
      (footprint "eagle-import:SOD123")
      (libsource (lib "eagle-import") (part "DIODE-SOD123"))
    )
    (comp (ref "D3")
      (value "DIODE-SOD123")
      (footprint "eagle-import:SOD123")
      (libsource (lib "eagle-import") (part "DIODE-SOD123"))
    )
    (comp (ref "IC4")
      (value "74AUC1G17DBV")
      (footprint "eagle-import:SOT23-5")
      (libsource (lib "eagle-import") (part "741G17DBVAUC"))
    )
    (comp (ref "IC5")
      (value "74HC590D")
      (footprint "eagle-import:SO16")
      (libsource (lib "eagle-import") (part "74590DHC"))
    )
    (comp (ref "IC6")
      (value "74HC541DW")
      (footprint "eagle-import:SO20W")
      (libsource (lib "eagle-import") (part "74541DWHC"))
    )
    (comp (ref "IC7")
      (value "74HC541DW")
      (footprint "eagle-import:SO20W")
      (libsource (lib "eagle-import") (part "74541DWHC"))
    )
    (comp (ref "JP1")
      (value "PINHD-1X2")
      (footprint "eagle-import:1X02")
      (libsource (lib "eagle-import") (part "PINHD-1X2"))
    )
    (comp (ref "JP2")
      (value "JP5Q")
      (footprint "eagle-import:JP5Q")
      (libsource (lib "eagle-import") (part "JP5Q"))
    )
    (comp (ref "LED2")
      (value "LED-5MM-GREEN")
      (footprint "eagle-import:CHIPLED_0805")
      (libsource (lib "eagle-import") (part "LEDCHIPLED_0805"))
    )
    (comp (ref "R4")
      (value "4k7")
      (footprint "eagle-import:R0805")
      (libsource (lib "eagle-import") (part "resistor_R-EU_R0805"))
    )
    (comp (ref "R8")
      (value "330R")
      (footprint "eagle-import:R0805")
      (libsource (lib "eagle-import") (part "resistor_R-EU_R0805"))
    )
    (comp (ref "R9")
      (value "50k")
      (footprint "eagle-import:R0805")
      (libsource (lib "eagle-import") (part "resistor_R-EU_R0805"))
    )
    (comp (ref "R10")
      (value "4k7")
      (footprint "eagle-import:R0805")
      (libsource (lib "eagle-import") (part "resistor_R-EU_R0805"))
    )
    (comp (ref "R13")
      (value "4k7")
      (footprint "eagle-import:R0805")
      (libsource (lib "eagle-import") (part "resistor_R-EU_R0805"))
    )
    (comp (ref "R14")
      (value "30R")
      (footprint "eagle-import:R0805")
      (libsource (lib "eagle-import") (part "resistor_R-EU_R0805"))
    )
    (comp (ref "S1")
      (value "TAC_SWITCHPTH")
      (footprint "eagle-import:TACTILE-PTH")
      (libsource (lib "eagle-import") (part "TAC_SWITCHPTH"))
    )
    (comp (ref "T2")
      (value "BC848")
      (footprint "eagle-import:SOT23")
      (libsource (lib "eagle-import") (part "BC848"))
    )
    (comp (ref "C5")
      (value "0.1uF")
      (footprint "eagle-import:C0805K")
      (libsource (lib "eagle-import") (part "C-EUC0805K"))
    )
    (comp (ref "C16")
      (value "0.1uF")
      (footprint "eagle-import:C0805K")
      (libsource (lib "eagle-import") (part "C-EUC0805K"))
    )
    (comp (ref "C35")
      (value "0.1uF")
      (footprint "eagle-import:C0805K")
      (libsource (lib "eagle-import") (part "C-EUC0805K"))
    )
    (comp (ref "C36")
      (value "0.1uF")
      (footprint "eagle-import:C0805K")
      (libsource (lib "eagle-import") (part "C-EUC0805K"))
    )
    (comp (ref "C37")
      (value "0.1uF")
      (footprint "eagle-import:C0805K")
      (libsource (lib "eagle-import") (part "C-EUC0805K"))
    )
    (comp (ref "C38")
      (value "0.1uF")
      (footprint "eagle-import:C0805K")
      (libsource (lib "eagle-import") (part "C-EUC0805K"))
    )
    (comp (ref "C39")
      (value "1uF")
      (footprint "eagle-import:C0805K")
      (libsource (lib "eagle-import") (part "C-EUC0805K"))
    )
    (comp (ref "IC8")
      (value "74HC541DW")
      (footprint "eagle-import:SO20W")
      (libsource (lib "eagle-import") (part "74541DWHC"))
    )
    (comp (ref "IC11")
      (value "74AHC1G04DBV")
      (footprint "eagle-import:SOT23-5")
      (libsource (lib "eagle-import") (part "741G04DBVAHC"))
    )
    (comp (ref "IC25")
      (value "74HC573D")
      (footprint "eagle-import:SO20W")
      (libsource (lib "eagle-import") (part "74573DHC"))
    )
    (comp (ref "IC26")
      (value "74HC573D")
      (footprint "eagle-import:SO20W")
      (libsource (lib "eagle-import") (part "74573DHC"))
    )
    (comp (ref "IC27")
      (value "74HC541DW")
      (footprint "eagle-import:SO20W")
      (libsource (lib "eagle-import") (part "74541DWHC"))
    )
    (comp (ref "R11")
      (value "30R")
      (footprint "eagle-import:R0805")
      (libsource (lib "eagle-import") (part "resistor_R-EU_R0805"))
    )
    (comp (ref "C21")
      (value "0.1uF")
      (footprint "eagle-import:C0805K")
      (libsource (lib "eagle-import") (part "C-EUC0805K"))
    )
    (comp (ref "C40")
      (value "0.1uF")
      (footprint "eagle-import:C0805K")
      (libsource (lib "eagle-import") (part "C-EUC0805K"))
    )
    (comp (ref "C44")
      (value "0.1uF")
      (footprint "eagle-import:C0805K")
      (libsource (lib "eagle-import") (part "C-EUC0805K"))
    )
    (comp (ref "C45")
      (value "1uF")
      (footprint "eagle-import:C0805K")
      (libsource (lib "eagle-import") (part "C-EUC0805K"))
    )
    (comp (ref "IC12")
      (value "74HC74D")
      (footprint "eagle-import:SO14")
      (libsource (lib "eagle-import") (part "7474DHC"))
    )
    (comp (ref "IC21")
      (value "74HC74D")
      (footprint "eagle-import:SO14")
      (libsource (lib "eagle-import") (part "7474DHC"))
    )
    (comp (ref "IC29")
      (value "74AHC1G08DBV")
      (footprint "eagle-import:SOT23-5")
      (libsource (lib "eagle-import") (part "741G08DBVAHC"))
    )
    (comp (ref "IC30")
      (value "74AHC1G32DBV")
      (footprint "eagle-import:SOT23-5")
      (libsource (lib "eagle-import") (part "741G32DBVAHC"))
    )
    (comp (ref "IC31")
      (value "74HC112D")
      (footprint "eagle-import:SO16")
      (libsource (lib "eagle-import") (part "74112DHC"))
    )
    (comp (ref "LED3")
      (value "LED-5MM-GREEN")
      (footprint "eagle-import:CHIPLED_0805")
      (libsource (lib "eagle-import") (part "LEDCHIPLED_0805"))
    )
    (comp (ref "LED4")
      (value "LED-5MM-GREEN")
      (footprint "eagle-import:CHIPLED_0805")
      (libsource (lib "eagle-import") (part "LEDCHIPLED_0805"))
    )
    (comp (ref "R48")
      (value "4k7")
      (footprint "eagle-import:R0805")
      (libsource (lib "eagle-import") (part "resistor_R-EU_R0805"))
    )
    (comp (ref "R49")
      (value "330R")
      (footprint "eagle-import:R0805")
      (libsource (lib "eagle-import") (part "resistor_R-EU_R0805"))
    )
    (comp (ref "R50")
      (value "330R")
      (footprint "eagle-import:R0805")
      (libsource (lib "eagle-import") (part "resistor_R-EU_R0805"))
    )
    (comp (ref "C22")
      (value "0.1uF")
      (footprint "eagle-import:C0805K")
      (libsource (lib "eagle-import") (part "C-EUC0805K"))
    )
    (comp (ref "C23")
      (value "0.1uF")
      (footprint "eagle-import:C0805K")
      (libsource (lib "eagle-import") (part "C-EUC0805K"))
    )
    (comp (ref "C24")
      (value "0.1uF")
      (footprint "eagle-import:C0805K")
      (libsource (lib "eagle-import") (part "C-EUC0805K"))
    )
    (comp (ref "C25")
      (value "0.1uF")
      (footprint "eagle-import:C0805K")
      (libsource (lib "eagle-import") (part "C-EUC0805K"))
    )
    (comp (ref "C26")
      (value "0.1uF")
      (footprint "eagle-import:C0805K")
      (libsource (lib "eagle-import") (part "C-EUC0805K"))
    )
    (comp (ref "C27")
      (value "0.1uF")
      (footprint "eagle-import:C0805K")
      (libsource (lib "eagle-import") (part "C-EUC0805K"))
    )
    (comp (ref "C28")
      (value "0.1uF")
      (footprint "eagle-import:C0805K")
      (libsource (lib "eagle-import") (part "C-EUC0805K"))
    )
    (comp (ref "C29")
      (value "0.1uF")
      (footprint "eagle-import:C0805K")
      (libsource (lib "eagle-import") (part "C-EUC0805K"))
    )
    (comp (ref "C30")
      (value "1uF")
      (footprint "eagle-import:C0805K")
      (libsource (lib "eagle-import") (part "C-EUC0805K"))
    )
    (comp (ref "IC13")
      (value "74HC08D")
      (footprint "eagle-import:SO14")
      (libsource (lib "eagle-import") (part "7408DHC"))
    )
    (comp (ref "IC14")
      (value "74HC32D")
      (footprint "eagle-import:SO14")
      (libsource (lib "eagle-import") (part "7432DHC"))
    )
    (comp (ref "IC15")
      (value "74AHC1G86DBV")
      (footprint "eagle-import:SOT23-5")
      (libsource (lib "eagle-import") (part "741G86DBVAHC"))
    )
    (comp (ref "IC16")
      (value "74HC32D")
      (footprint "eagle-import:SO14")
      (libsource (lib "eagle-import") (part "7432DHC"))
    )
    (comp (ref "IC17")
      (value "74AHC1G04DBV")
      (footprint "eagle-import:SOT23-5")
      (libsource (lib "eagle-import") (part "741G04DBVAHC"))
    )
    (comp (ref "IC18")
      (value "74HC251D")
      (footprint "eagle-import:SO16")
      (libsource (lib "eagle-import") (part "74251DHC"))
    )
    (comp (ref "IC19")
      (value "74HC251D")
      (footprint "eagle-import:SO16")
      (libsource (lib "eagle-import") (part "74251DHC"))
    )
    (comp (ref "IC20")
      (value "74AC1G11DBV")
      (footprint "eagle-import:DBV_R-PDSO-G6")
      (libsource (lib "eagle-import") (part "741G11DBVAC"))
    )
    (comp (ref "R6")
      (value "4k7")
      (footprint "eagle-import:R0805")
      (libsource (lib "eagle-import") (part "R-EU_R0805"))
    )
    (comp (ref "R7")
      (value "4k7")
      (footprint "eagle-import:R0805")
      (libsource (lib "eagle-import") (part "R-EU_R0805"))
    )
    (comp (ref "R40")
      (value "4k7")
      (footprint "eagle-import:R0805")
      (libsource (lib "eagle-import") (part "R-EU_R0805"))
    )
    (comp (ref "R41")
      (value "30R")
      (footprint "eagle-import:R0805")
      (libsource (lib "eagle-import") (part "resistor_R-EU_R0805"))
    )
  )
  (nets
    (net (code "22") (name "*TPA") (class "Default")
      (node (ref "EXP1") (pin "A17") (pinfunction "17_A17") (pintype "passive"))
    )
    (net (code "23") (name "*TPC") (class "Default")
      (node (ref "EXP1") (pin "C17") (pinfunction "17_C17") (pintype "passive"))
    )
    (net (code "24") (name "+3.3V") (class "Default")
      (node (ref "EXP1") (pin "A4") (pinfunction "4_A4") (pintype "passive"))
      (node (ref "EXP1") (pin "B4") (pinfunction "4_B4") (pintype "passive"))
      (node (ref "EXP1") (pin "C4") (pinfunction "4_C4") (pintype "passive"))
    )
    (net (code "25") (name "+12V") (class "Default")
      (node (ref "EXP1") (pin "A31") (pinfunction "31_A31") (pintype "passive"))
      (node (ref "EXP1") (pin "B31") (pinfunction "31_B31") (pintype "passive"))
      (node (ref "EXP1") (pin "C31") (pinfunction "31_C31") (pintype "passive"))
    )
    (net (code "38") (name "AB0") (class "Default")
      (node (ref "EXP1") (pin "A5") (pinfunction "5_A5") (pintype "passive"))
    )
    (net (code "39") (name "AB1") (class "Default")
      (node (ref "EXP1") (pin "A6") (pinfunction "6_A6") (pintype "passive"))
    )
    (net (code "40") (name "AB2") (class "Default")
      (node (ref "EXP1") (pin "A7") (pinfunction "7_A7") (pintype "passive"))
    )
    (net (code "41") (name "AB3") (class "Default")
      (node (ref "EXP1") (pin "A8") (pinfunction "8_A8") (pintype "passive"))
    )
    (net (code "42") (name "AB4") (class "Default")
      (node (ref "EXP1") (pin "A9") (pinfunction "9_A9") (pintype "passive"))
    )
    (net (code "43") (name "AB5") (class "Default")
      (node (ref "EXP1") (pin "A10") (pinfunction "10_A10") (pintype "passive"))
    )
    (net (code "44") (name "AB6") (class "Default")
      (node (ref "EXP1") (pin "A11") (pinfunction "11_A11") (pintype "passive"))
    )
    (net (code "45") (name "AB7") (class "Default")
      (node (ref "EXP1") (pin "A12") (pinfunction "12_A12") (pintype "passive"))
    )
    (net (code "46") (name "AB8") (class "Default")
      (node (ref "EXP1") (pin "A20") (pinfunction "20_A20") (pintype "passive"))
    )
    (net (code "47") (name "AB9") (class "Default")
      (node (ref "EXP1") (pin "A21") (pinfunction "21_A21") (pintype "passive"))
    )
    (net (code "48") (name "AB10") (class "Default")
      (node (ref "EXP1") (pin "A22") (pinfunction "22_A22") (pintype "passive"))
    )
    (net (code "49") (name "AB11") (class "Default")
      (node (ref "EXP1") (pin "A23") (pinfunction "23_A23") (pintype "passive"))
    )
    (net (code "50") (name "AB12") (class "Default")
      (node (ref "EXP1") (pin "A24") (pinfunction "24_A24") (pintype "passive"))
    )
    (net (code "51") (name "AB13") (class "Default")
      (node (ref "EXP1") (pin "A25") (pinfunction "25_A25") (pintype "passive"))
    )
    (net (code "52") (name "AB14") (class "Default")
      (node (ref "EXP1") (pin "A26") (pinfunction "26_A26") (pintype "passive"))
    )
    (net (code "53") (name "AB15") (class "Default")
      (node (ref "EXP1") (pin "A27") (pinfunction "27_A27") (pintype "passive"))
    )
    (net (code "54") (name "AC0") (class "Default")
      (node (ref "P1") (pin "23") (pinfunction "KL_23") (pintype "passive"))
    )
    (net (code "55") (name "AC1") (class "Default")
      (node (ref "P1") (pin "24") (pinfunction "KL_24") (pintype "passive"))
    )
    (net (code "56") (name "AC2") (class "Default")
      (node (ref "P1") (pin "25") (pinfunction "KL_25") (pintype "passive"))
    )
    (net (code "57") (name "AC3") (class "Default")
      (node (ref "P1") (pin "26") (pinfunction "KL_26") (pintype "passive"))
    )
    (net (code "58") (name "AC4") (class "Default")
      (node (ref "P1") (pin "27") (pinfunction "KL_27") (pintype "passive"))
    )
    (net (code "59") (name "AC5") (class "Default")
      (node (ref "P1") (pin "28") (pinfunction "KL_28") (pintype "passive"))
    )
    (net (code "60") (name "AC6") (class "Default")
      (node (ref "P1") (pin "29") (pinfunction "KL_29") (pintype "passive"))
    )
    (net (code "61") (name "AC7") (class "Default")
      (node (ref "P1") (pin "30") (pinfunction "KL_30") (pintype "passive"))
    )
    (net (code "62") (name "AC8") (class "Default")
      (node (ref "P1") (pin "31") (pinfunction "KL_31") (pintype "passive"))
    )
    (net (code "63") (name "AC9") (class "Default")
      (node (ref "P1") (pin "32") (pinfunction "KL_32") (pintype "passive"))
    )
    (net (code "64") (name "AC10") (class "Default")
      (node (ref "P1") (pin "33") (pinfunction "KL_33") (pintype "passive"))
    )
    (net (code "65") (name "AC11") (class "Default")
      (node (ref "P1") (pin "34") (pinfunction "KL_34") (pintype "passive"))
    )
    (net (code "66") (name "AC12") (class "Default")
      (node (ref "P1") (pin "35") (pinfunction "KL_35") (pintype "passive"))
    )
    (net (code "67") (name "AC13") (class "Default")
      (node (ref "P1") (pin "36") (pinfunction "KL_36") (pintype "passive"))
    )
    (net (code "68") (name "AC14") (class "Default")
      (node (ref "P1") (pin "37") (pinfunction "KL_37") (pintype "passive"))
    )
    (net (code "69") (name "AC15") (class "Default")
      (node (ref "P1") (pin "38") (pinfunction "KL_38") (pintype "passive"))
    )
    (net (code "70") (name "AEXT0") (class "Default")
      (node (ref "EXP1") (pin "B13") (pinfunction "13_B13") (pintype "passive"))
    )
    (net (code "71") (name "AEXT1") (class "Default")
      (node (ref "EXP1") (pin "B14") (pinfunction "14_B14") (pintype "passive"))
    )
    (net (code "72") (name "AEXT2") (class "Default")
      (node (ref "EXP1") (pin "B15") (pinfunction "15_B15") (pintype "passive"))
    )
    (net (code "73") (name "AEXT3") (class "Default")
      (node (ref "EXP1") (pin "B16") (pinfunction "16_B16") (pintype "passive"))
    )
    (net (code "74") (name "AEXT4") (class "Default")
      (node (ref "EXP1") (pin "B17") (pinfunction "17_B17") (pintype "passive"))
    )
    (net (code "75") (name "AEXT5") (class "Default")
      (node (ref "EXP1") (pin "B18") (pinfunction "18_B18") (pintype "passive"))
    )
    (net (code "76") (name "AEXT6") (class "Default")
      (node (ref "EXP1") (pin "B19") (pinfunction "19_B19") (pintype "passive"))
    )
    (net (code "77") (name "AEXT7") (class "Default")
      (node (ref "EXP1") (pin "B20") (pinfunction "20_B20") (pintype "passive"))
    )
    (net (code "78") (name "BFIRQ") (class "Default")
      (node (ref "IC9") (pin "6") (pinfunction "O_6") (pintype "output"))
      (node (ref "P3") (pin "35") (pinfunction "KL_35") (pintype "passive"))
    )
    (net (code "79") (name "BFNEG") (class "Default")
      (node (ref "IC9") (pin "4") (pinfunction "O_4") (pintype "output"))
      (node (ref "P3") (pin "37") (pinfunction "KL_37") (pintype "passive"))
    )
    (net (code "80") (name "BFZERO") (class "Default")
      (node (ref "IC9") (pin "2") (pinfunction "O_2") (pintype "output"))
      (node (ref "P3") (pin "39") (pinfunction "KL_39") (pintype "passive"))
    )
    (net (code "81") (name "CLK1") (class "Default")
      (node (ref "EXP1") (pin "A29") (pinfunction "29_A29") (pintype "passive"))
      (node (ref "IC3") (pin "4") (pinfunction "Y0_4") (pintype "output"))
    )
    (net (code "82") (name "CLK2") (class "Default")
      (node (ref "EXP1") (pin "B29") (pinfunction "29_B29") (pintype "passive"))
      (node (ref "IC3") (pin "5") (pinfunction "Y1_5") (pintype "output"))
      (node (ref "IC33") (pin "3") (pinfunction "CLK_3") (pintype "input"))
    )
    (net (code "83") (name "CLK3") (class "Default")
      (node (ref "EXP1") (pin "B30") (pinfunction "30_B30") (pintype "passive"))
      (node (ref "IC3") (pin "6") (pinfunction "Y2_6") (pintype "output"))
      (node (ref "IC5") (pin "11") (pinfunction "CLK_11") (pintype "input"))
      (node (ref "IC5") (pin "13") (pinfunction "RCK_13") (pintype "input"))
    )
    (net (code "84") (name "CLK4") (class "Default")
      (node (ref "EXP1") (pin "B28") (pinfunction "28_B28") (pintype "passive"))
      (node (ref "IC21") (pin "3") (pinfunction "CLK_3") (pintype "input"))
      (node (ref "IC3") (pin "7") (pinfunction "Y3_7") (pintype "output"))
      (node (ref "IC38") (pin "1") (pinfunction "I0_1") (pintype "input"))
    )
    (net (code "85") (name "DB0") (class "Default")
      (node (ref "EXP1") (pin "C5") (pinfunction "5_C5") (pintype "passive"))
      (node (ref "IC35") (pin "18") (pinfunction "B1_18") (pintype "bidirectional"))
    )
    (net (code "86") (name "DB1") (class "Default")
      (node (ref "EXP1") (pin "C6") (pinfunction "6_C6") (pintype "passive"))
      (node (ref "IC35") (pin "17") (pinfunction "B2_17") (pintype "bidirectional"))
    )
    (net (code "87") (name "DB2") (class "Default")
      (node (ref "EXP1") (pin "C7") (pinfunction "7_C7") (pintype "passive"))
      (node (ref "IC35") (pin "16") (pinfunction "B3_16") (pintype "bidirectional"))
    )
    (net (code "88") (name "DB3") (class "Default")
      (node (ref "EXP1") (pin "C8") (pinfunction "8_C8") (pintype "passive"))
      (node (ref "IC35") (pin "15") (pinfunction "B4_15") (pintype "bidirectional"))
    )
    (net (code "89") (name "DB4") (class "Default")
      (node (ref "EXP1") (pin "C9") (pinfunction "9_C9") (pintype "passive"))
      (node (ref "IC35") (pin "14") (pinfunction "B5_14") (pintype "bidirectional"))
    )
    (net (code "90") (name "DB5") (class "Default")
      (node (ref "EXP1") (pin "C10") (pinfunction "10_C10") (pintype "passive"))
      (node (ref "IC35") (pin "13") (pinfunction "B6_13") (pintype "bidirectional"))
    )
    (net (code "91") (name "DB6") (class "Default")
      (node (ref "EXP1") (pin "C11") (pinfunction "11_C11") (pintype "passive"))
      (node (ref "IC35") (pin "12") (pinfunction "B7_12") (pintype "bidirectional"))
    )
    (net (code "92") (name "DB7") (class "Default")
      (node (ref "EXP1") (pin "C12") (pinfunction "12_C12") (pintype "passive"))
      (node (ref "IC35") (pin "11") (pinfunction "B8_11") (pintype "bidirectional"))
    )
    (net (code "93") (name "DB8") (class "Default")
      (node (ref "EXP1") (pin "C21") (pinfunction "21_C21") (pintype "passive"))
      (node (ref "IC36") (pin "18") (pinfunction "B1_18") (pintype "bidirectional"))
    )
    (net (code "94") (name "DB9") (class "Default")
      (node (ref "EXP1") (pin "C22") (pinfunction "22_C22") (pintype "passive"))
      (node (ref "IC36") (pin "17") (pinfunction "B2_17") (pintype "bidirectional"))
    )
    (net (code "95") (name "DB10") (class "Default")
      (node (ref "EXP1") (pin "C23") (pinfunction "23_C23") (pintype "passive"))
      (node (ref "IC36") (pin "16") (pinfunction "B3_16") (pintype "bidirectional"))
    )
    (net (code "96") (name "DB11") (class "Default")
      (node (ref "EXP1") (pin "C24") (pinfunction "24_C24") (pintype "passive"))
      (node (ref "IC36") (pin "15") (pinfunction "B4_15") (pintype "bidirectional"))
    )
    (net (code "97") (name "DB12") (class "Default")
      (node (ref "EXP1") (pin "C25") (pinfunction "25_C25") (pintype "passive"))
      (node (ref "IC36") (pin "14") (pinfunction "B5_14") (pintype "bidirectional"))
    )
    (net (code "98") (name "DB13") (class "Default")
      (node (ref "EXP1") (pin "C26") (pinfunction "26_C26") (pintype "passive"))
      (node (ref "IC36") (pin "13") (pinfunction "B6_13") (pintype "bidirectional"))
    )
    (net (code "99") (name "DB14") (class "Default")
      (node (ref "EXP1") (pin "C27") (pinfunction "27_C27") (pintype "passive"))
      (node (ref "IC36") (pin "12") (pinfunction "B7_12") (pintype "bidirectional"))
    )
    (net (code "100") (name "DB15") (class "Default")
      (node (ref "EXP1") (pin "C28") (pinfunction "28_C28") (pintype "passive"))
      (node (ref "IC36") (pin "11") (pinfunction "B8_11") (pintype "bidirectional"))
    )
    (net (code "101") (name "FINT") (class "Default")
      (node (ref "IC31") (pin "5") (pinfunction "Q_5") (pintype "output"))
      (node (ref "R49") (pin "2") (pinfunction "2_2") (pintype "passive"))
    )
    (net (code "102") (name "FIRQ") (class "Default")
      (node (ref "IC21") (pin "12") (pinfunction "D_12") (pintype "input"))
      (node (ref "IC31") (pin "9") (pinfunction "Q_9") (pintype "output"))
      (node (ref "IC9") (pin "9") (pinfunction "I_9") (pintype "input"))
    )
    (net (code "103") (name "FL") (class "Default")
      (node (ref "IC13") (pin "5") (pinfunction "I1_5") (pintype "input"))
      (node (ref "IC19") (pin "1") (pinfunction "I3_1") (pintype "input"))
      (node (ref "P1") (pin "5") (pinfunction "KL_5") (pintype "passive"))
    )
    (net (code "104") (name "FNEG") (class "Default")
      (node (ref "IC13") (pin "13") (pinfunction "I1_13") (pintype "input"))
      (node (ref "IC19") (pin "14") (pinfunction "I5_14") (pintype "input"))
      (node (ref "IC9") (pin "11") (pinfunction "I_11") (pintype "input"))
      (node (ref "P2") (pin "11") (pinfunction "KL_11") (pintype "passive"))
    )
    (net (code "105") (name "FPCLKEN") (class "Default")
      (node (ref "IC1") (pin "2") (pinfunction "B_2") (pintype "input"))
      (node (ref "P3") (pin "20") (pinfunction "KL_20") (pintype "passive"))
      (node (ref "R1") (pin "1") (pinfunction "1_1") (pintype "passive"))
      (node (ref "R15") (pin "2") (pinfunction "2_2") (pintype "passive"))
    )
    (net (code "106") (name "FPIR0") (class "Default")
      (node (ref "IC8") (pin "18") (pinfunction "Y1_18") (pintype "tri_state"))
      (node (ref "P3") (pin "31") (pinfunction "KL_31") (pintype "passive"))
    )
    (net (code "107") (name "FPIR1") (class "Default")
      (node (ref "IC8") (pin "17") (pinfunction "Y2_17") (pintype "tri_state"))
      (node (ref "P3") (pin "29") (pinfunction "KL_29") (pintype "passive"))
    )
    (net (code "108") (name "FPIR2") (class "Default")
      (node (ref "IC8") (pin "16") (pinfunction "Y3_16") (pintype "tri_state"))
      (node (ref "P3") (pin "27") (pinfunction "KL_27") (pintype "passive"))
    )
    (net (code "109") (name "FPIR3") (class "Default")
      (node (ref "IC8") (pin "15") (pinfunction "Y4_15") (pintype "tri_state"))
      (node (ref "P3") (pin "25") (pinfunction "KL_25") (pintype "passive"))
    )
    (net (code "110") (name "FPIR4") (class "Default")
      (node (ref "IC8") (pin "14") (pinfunction "Y5_14") (pintype "tri_state"))
      (node (ref "P3") (pin "23") (pinfunction "KL_23") (pintype "passive"))
    )
    (net (code "111") (name "FPIR5") (class "Default")
      (node (ref "IC8") (pin "13") (pinfunction "Y6_13") (pintype "tri_state"))
      (node (ref "P3") (pin "21") (pinfunction "KL_21") (pintype "passive"))
    )
    (net (code "112") (name "FPIR6") (class "Default")
      (node (ref "IC8") (pin "12") (pinfunction "Y7_12") (pintype "tri_state"))
      (node (ref "P3") (pin "19") (pinfunction "KL_19") (pintype "passive"))
    )
    (net (code "113") (name "FPIR7") (class "Default")
      (node (ref "IC8") (pin "11") (pinfunction "Y8_11") (pintype "tri_state"))
      (node (ref "P3") (pin "17") (pinfunction "KL_17") (pintype "passive"))
    )
    (net (code "114") (name "FPIR8") (class "Default")
      (node (ref "IC27") (pin "18") (pinfunction "Y1_18") (pintype "tri_state"))
      (node (ref "P3") (pin "15") (pinfunction "KL_15") (pintype "passive"))
    )
    (net (code "115") (name "FPIR9") (class "Default")
      (node (ref "IC27") (pin "17") (pinfunction "Y2_17") (pintype "tri_state"))
      (node (ref "P3") (pin "13") (pinfunction "KL_13") (pintype "passive"))
    )
    (net (code "116") (name "FPIR10") (class "Default")
      (node (ref "IC27") (pin "16") (pinfunction "Y3_16") (pintype "tri_state"))
      (node (ref "P3") (pin "11") (pinfunction "KL_11") (pintype "passive"))
    )
    (net (code "117") (name "FPIR11") (class "Default")
      (node (ref "IC27") (pin "15") (pinfunction "Y4_15") (pintype "tri_state"))
      (node (ref "P3") (pin "9") (pinfunction "KL_9") (pintype "passive"))
    )
    (net (code "118") (name "FPIR12") (class "Default")
      (node (ref "IC27") (pin "14") (pinfunction "Y5_14") (pintype "tri_state"))
      (node (ref "P3") (pin "7") (pinfunction "KL_7") (pintype "passive"))
    )
    (net (code "119") (name "FPIR13") (class "Default")
      (node (ref "IC27") (pin "13") (pinfunction "Y6_13") (pintype "tri_state"))
      (node (ref "P3") (pin "5") (pinfunction "KL_5") (pintype "passive"))
    )
    (net (code "120") (name "FPIR14") (class "Default")
      (node (ref "IC27") (pin "12") (pinfunction "Y7_12") (pintype "tri_state"))
      (node (ref "P3") (pin "3") (pinfunction "KL_3") (pintype "passive"))
    )
    (net (code "121") (name "FPIR15") (class "Default")
      (node (ref "IC27") (pin "11") (pinfunction "Y8_11") (pintype "tri_state"))
      (node (ref "P3") (pin "1") (pinfunction "KL_1") (pintype "passive"))
    )
    (net (code "122") (name "FPUSTEP") (class "Default")
      (node (ref "IC1") (pin "14") (pinfunction "A_14") (pintype "input"))
      (node (ref "P3") (pin "22") (pinfunction "KL_22") (pintype "passive"))
      (node (ref "R2") (pin "2") (pinfunction "2_2") (pintype "passive"))
    )
    (net (code "123") (name "FV") (class "Default")
      (node (ref "IC13") (pin "2") (pinfunction "I1_2") (pintype "input"))
      (node (ref "IC19") (pin "2") (pinfunction "I2_2") (pintype "input"))
      (node (ref "P1") (pin "6") (pinfunction "KL_6") (pintype "passive"))
    )
    (net (code "124") (name "FZERO") (class "Default")
      (node (ref "IC13") (pin "10") (pinfunction "I1_10") (pintype "input"))
      (node (ref "IC19") (pin "15") (pinfunction "I4_15") (pintype "input"))
      (node (ref "IC9") (pin "13") (pinfunction "I_13") (pintype "input"))
      (node (ref "P2") (pin "12") (pinfunction "KL_12") (pintype "passive"))
    )
    (net (code "125") (name "GND") (class "Default")
      (node (ref "C1") (pin "1") (pinfunction "1_1") (pintype "passive"))
      (node (ref "C10") (pin "-") (pinfunction "-_-") (pintype "passive"))
      (node (ref "C11") (pin "1") (pinfunction "1_1") (pintype "passive"))
      (node (ref "C12") (pin "1") (pinfunction "1_1") (pintype "passive"))
      (node (ref "C13") (pin "1") (pinfunction "1_1") (pintype "passive"))
      (node (ref "C14") (pin "-") (pinfunction "-_-") (pintype "passive"))
      (node (ref "C15") (pin "1") (pinfunction "1_1") (pintype "passive"))
      (node (ref "C16") (pin "1") (pinfunction "1_1") (pintype "passive"))
      (node (ref "C2") (pin "1") (pinfunction "1_1") (pintype "passive"))
      (node (ref "C21") (pin "1") (pinfunction "1_1") (pintype "passive"))
      (node (ref "C22") (pin "1") (pinfunction "1_1") (pintype "passive"))
      (node (ref "C23") (pin "1") (pinfunction "1_1") (pintype "passive"))
      (node (ref "C24") (pin "1") (pinfunction "1_1") (pintype "passive"))
      (node (ref "C25") (pin "1") (pinfunction "1_1") (pintype "passive"))
      (node (ref "C26") (pin "1") (pinfunction "1_1") (pintype "passive"))
      (node (ref "C27") (pin "1") (pinfunction "1_1") (pintype "passive"))
      (node (ref "C28") (pin "1") (pinfunction "1_1") (pintype "passive"))
      (node (ref "C29") (pin "1") (pinfunction "1_1") (pintype "passive"))
      (node (ref "C3") (pin "1") (pinfunction "1_1") (pintype "passive"))
      (node (ref "C30") (pin "1") (pinfunction "1_1") (pintype "passive"))
      (node (ref "C31") (pin "1") (pinfunction "1_1") (pintype "passive"))
      (node (ref "C32") (pin "1") (pinfunction "1_1") (pintype "passive"))
      (node (ref "C33") (pin "1") (pinfunction "1_1") (pintype "passive"))
      (node (ref "C34") (pin "1") (pinfunction "1_1") (pintype "passive"))
      (node (ref "C35") (pin "1") (pinfunction "1_1") (pintype "passive"))
      (node (ref "C36") (pin "1") (pinfunction "1_1") (pintype "passive"))
      (node (ref "C37") (pin "1") (pinfunction "1_1") (pintype "passive"))
      (node (ref "C38") (pin "1") (pinfunction "1_1") (pintype "passive"))
      (node (ref "C39") (pin "1") (pinfunction "1_1") (pintype "passive"))
      (node (ref "C4") (pin "1") (pinfunction "1_1") (pintype "passive"))
      (node (ref "C40") (pin "1") (pinfunction "1_1") (pintype "passive"))
      (node (ref "C44") (pin "1") (pinfunction "1_1") (pintype "passive"))
      (node (ref "C45") (pin "1") (pinfunction "1_1") (pintype "passive"))
      (node (ref "C46") (pin "1") (pinfunction "1_1") (pintype "passive"))
      (node (ref "C47") (pin "1") (pinfunction "1_1") (pintype "passive"))
      (node (ref "C48") (pin "1") (pinfunction "1_1") (pintype "passive"))
      (node (ref "C49") (pin "1") (pinfunction "1_1") (pintype "passive"))
      (node (ref "C5") (pin "1") (pinfunction "1_1") (pintype "passive"))
      (node (ref "C50") (pin "1") (pinfunction "1_1") (pintype "passive"))
      (node (ref "C51") (pin "1") (pinfunction "1_1") (pintype "passive"))
      (node (ref "C52") (pin "1") (pinfunction "1_1") (pintype "passive"))
      (node (ref "C53") (pin "1") (pinfunction "1_1") (pintype "passive"))
      (node (ref "C54") (pin "1") (pinfunction "1_1") (pintype "passive"))
      (node (ref "C55") (pin "1") (pinfunction "1_1") (pintype "passive"))
      (node (ref "C56") (pin "1") (pinfunction "1_1") (pintype "passive"))
      (node (ref "C57") (pin "-") (pinfunction "-_-") (pintype "passive"))
      (node (ref "C6") (pin "1") (pinfunction "1_1") (pintype "passive"))
      (node (ref "C7") (pin "1") (pinfunction "1_1") (pintype "passive"))
      (node (ref "C8") (pin "1") (pinfunction "1_1") (pintype "passive"))
      (node (ref "C9") (pin "1") (pinfunction "1_1") (pintype "passive"))
      (node (ref "EXP1") (pin "A1") (pinfunction "1_A1") (pintype "passive"))
      (node (ref "EXP1") (pin "A2") (pinfunction "2_A2") (pintype "passive"))
      (node (ref "EXP1") (pin "B1") (pinfunction "1_B1") (pintype "passive"))
      (node (ref "EXP1") (pin "B2") (pinfunction "2_B2") (pintype "passive"))
      (node (ref "EXP1") (pin "C1") (pinfunction "1_C1") (pintype "passive"))
      (node (ref "EXP1") (pin "C2") (pinfunction "2_C2") (pintype "passive"))
      (node (ref "IC1") (pin "1") (pinfunction "1G_1") (pintype "input"))
      (node (ref "IC1") (pin "10") (pinfunction "2C0_10") (pintype "input"))
      (node (ref "IC1") (pin "11") (pinfunction "2C1_11") (pintype "input"))
      (node (ref "IC1") (pin "12") (pinfunction "2C2_12") (pintype "input"))
      (node (ref "IC1") (pin "13") (pinfunction "2C3_13") (pintype "input"))
      (node (ref "IC1") (pin "15") (pinfunction "2G_15") (pintype "input"))
      (node (ref "IC1") (pin "6") (pinfunction "1C0_6") (pintype "input"))
      (node (ref "IC12") (pin "12") (pinfunction "D_12") (pintype "input"))
      (node (ref "IC14") (pin "12") (pinfunction "I0_12") (pintype "input"))
      (node (ref "IC14") (pin "13") (pinfunction "I1_13") (pintype "input"))
      (node (ref "IC18") (pin "4") (pinfunction "I0_4") (pintype "input"))
      (node (ref "IC19") (pin "3") (pinfunction "I1_3") (pintype "input"))
      (node (ref "IC19") (pin "4") (pinfunction "I0_4") (pintype "input"))
      (node (ref "IC2") (pin "1") (pinfunction "B_1") (pintype "input"))
      (node (ref "IC2") (pin "10") (pinfunction "C_10") (pintype "input"))
      (node (ref "IC2") (pin "14") (pinfunction "CLEAR_14") (pintype "input"))
      (node (ref "IC2") (pin "15") (pinfunction "A_15") (pintype "input"))
      (node (ref "IC2") (pin "9") (pinfunction "D_9") (pintype "input"))
      (node (ref "IC22") (pin "8") (pinfunction "7D_8") (pintype "input"))
      (node (ref "IC22") (pin "9") (pinfunction "8D_9") (pintype "input"))
      (node (ref "IC23") (pin "19") (pinfunction "G2_19") (pintype "input"))
      (node (ref "IC24") (pin "19") (pinfunction "G2_19") (pintype "input"))
      (node (ref "IC25") (pin "1") (pinfunction "~{OE}_1") (pintype "input"))
      (node (ref "IC26") (pin "1") (pinfunction "~{OE}_1") (pintype "input"))
      (node (ref "IC27") (pin "1") (pinfunction "G1_1") (pintype "input"))
      (node (ref "IC27") (pin "19") (pinfunction "G2_19") (pintype "input"))
      (node (ref "IC3") (pin "1") (pinfunction "G_1") (pintype "input"))
      (node (ref "IC3") (pin "13") (pinfunction "B_13") (pintype "input"))
      (node (ref "IC3") (pin "15") (pinfunction "G_15") (pintype "input"))
      (node (ref "IC31") (pin "1") (pinfunction "CLK_1") (pintype "input"))
      (node (ref "IC31") (pin "11") (pinfunction "J_11") (pintype "input"))
      (node (ref "IC31") (pin "12") (pinfunction "K_12") (pintype "input"))
      (node (ref "IC31") (pin "13") (pinfunction "CLK_13") (pintype "input"))
      (node (ref "IC31") (pin "2") (pinfunction "K_2") (pintype "input"))
      (node (ref "IC31") (pin "3") (pinfunction "J_3") (pintype "input"))
      (node (ref "IC33") (pin "10") (pinfunction "PRE_10") (pintype "input"))
      (node (ref "IC33") (pin "11") (pinfunction "CLK_11") (pintype "input"))
      (node (ref "IC33") (pin "12") (pinfunction "D_12") (pintype "input"))
      (node (ref "IC33") (pin "13") (pinfunction "CLR_13") (pintype "input"))
      (node (ref "IC33") (pin "2") (pinfunction "D_2") (pintype "input"))
      (node (ref "IC41") (pin "13") (pinfunction "D9_13") (pintype "input"))
      (node (ref "IC41") (pin "14") (pinfunction "D10_14") (pintype "input"))
      (node (ref "IC42") (pin "13") (pinfunction "D9_13") (pintype "input"))
      (node (ref "IC42") (pin "14") (pinfunction "D10_14") (pintype "input"))
      (node (ref "IC5") (pin "14") (pinfunction "G_14") (pintype "input"))
      (node (ref "IC6") (pin "2") (pinfunction "A1_2") (pintype "input"))
      (node (ref "IC6") (pin "3") (pinfunction "A2_3") (pintype "input"))
      (node (ref "IC6") (pin "4") (pinfunction "A3_4") (pintype "input"))
      (node (ref "IC6") (pin "5") (pinfunction "A4_5") (pintype "input"))
      (node (ref "IC8") (pin "1") (pinfunction "G1_1") (pintype "input"))
      (node (ref "IC8") (pin "19") (pinfunction "G2_19") (pintype "input"))
      (node (ref "JP1") (pin "1") (pinfunction "1_1") (pintype "passive"))
      (node (ref "LED3") (pin "C") (pinfunction "C_C") (pintype "passive"))
      (node (ref "LED4") (pin "C") (pinfunction "C_C") (pintype "passive"))
      (node (ref "P3") (pin "10") (pinfunction "KL_10") (pintype "passive"))
      (node (ref "P3") (pin "12") (pinfunction "KL_12") (pintype "passive"))
      (node (ref "P3") (pin "14") (pinfunction "KL_14") (pintype "passive"))
      (node (ref "P3") (pin "16") (pinfunction "KL_16") (pintype "passive"))
      (node (ref "P3") (pin "18") (pinfunction "KL_18") (pintype "passive"))
      (node (ref "P3") (pin "2") (pinfunction "KL_2") (pintype "passive"))
      (node (ref "P3") (pin "24") (pinfunction "KL_24") (pintype "passive"))
      (node (ref "P3") (pin "26") (pinfunction "KL_26") (pintype "passive"))
      (node (ref "P3") (pin "32") (pinfunction "KL_32") (pintype "passive"))
      (node (ref "P3") (pin "34") (pinfunction "KL_34") (pintype "passive"))
      (node (ref "P3") (pin "36") (pinfunction "KL_36") (pintype "passive"))
      (node (ref "P3") (pin "38") (pinfunction "KL_38") (pintype "passive"))
      (node (ref "P3") (pin "4") (pinfunction "KL_4") (pintype "passive"))
      (node (ref "P3") (pin "40") (pinfunction "KL_40") (pintype "passive"))
      (node (ref "P3") (pin "6") (pinfunction "KL_6") (pintype "passive"))
      (node (ref "P3") (pin "8") (pinfunction "KL_8") (pintype "passive"))
      (node (ref "R2") (pin "1") (pinfunction "1_1") (pintype "passive"))
      (node (ref "R4") (pin "1") (pinfunction "1_1") (pintype "passive"))
      (node (ref "R5") (pin "2") (pinfunction "2_2") (pintype "passive"))
      (node (ref "RN1") (pin "1") (pinfunction "1_1") (pintype "passive"))
      (node (ref "RN1") (pin "2") (pinfunction "2_2") (pintype "passive"))
      (node (ref "RN1") (pin "3") (pinfunction "3_3") (pintype "passive"))
      (node (ref "RN1") (pin "4") (pinfunction "4_4") (pintype "passive"))
      (node (ref "RN19") (pin "1") (pinfunction "1_1") (pintype "passive"))
      (node (ref "RN19") (pin "2") (pinfunction "2_2") (pintype "passive"))
      (node (ref "RN19") (pin "3") (pinfunction "3_3") (pintype "passive"))
      (node (ref "RN19") (pin "4") (pinfunction "4_4") (pintype "passive"))
      (node (ref "S1") (pin "1") (pinfunction "1_1") (pintype "passive"))
      (node (ref "S1") (pin "2") (pinfunction "2_2") (pintype "passive"))
      (node (ref "T1") (pin "2") (pinfunction "E_2") (pintype "passive"))
      (node (ref "T2") (pin "2") (pinfunction "E_2") (pintype "passive"))
      (node (ref "XTAL1") (pin "4") (pinfunction "GND_4") (pintype "power_in"))
    )
    (net (code "126") (name "HALT") (class "Default")
      (node (ref "IC10") (pin "1") (pinfunction "OE_1") (pintype "input"))
      (node (ref "IC28") (pin "4") (pinfunction "O_4") (pintype "output"))
    )
    (net (code "127") (name "IBUS0") (class "Default")
      (node (ref "IC23") (pin "18") (pinfunction "Y1_18") (pintype "tri_state"))
      (node (ref "IC25") (pin "2") (pinfunction "1D_2") (pintype "input"))
      (node (ref "IC35") (pin "2") (pinfunction "A1_2") (pintype "bidirectional"))
      (node (ref "IC41") (pin "1") (pinfunction "D1_1") (pintype "input"))
      (node (ref "IC6") (pin "18") (pinfunction "Y1_18") (pintype "tri_state"))
      (node (ref "P2") (pin "21") (pinfunction "KL_21") (pintype "passive"))
    )
    (net (code "128") (name "IBUS1") (class "Default")
      (node (ref "IC23") (pin "17") (pinfunction "Y2_17") (pintype "tri_state"))
      (node (ref "IC25") (pin "3") (pinfunction "2D_3") (pintype "input"))
      (node (ref "IC35") (pin "3") (pinfunction "A2_3") (pintype "bidirectional"))
      (node (ref "IC41") (pin "2") (pinfunction "D2_2") (pintype "input"))
      (node (ref "IC6") (pin "17") (pinfunction "Y2_17") (pintype "tri_state"))
      (node (ref "P2") (pin "22") (pinfunction "KL_22") (pintype "passive"))
    )
    (net (code "129") (name "IBUS2") (class "Default")
      (node (ref "IC23") (pin "16") (pinfunction "Y3_16") (pintype "tri_state"))
      (node (ref "IC25") (pin "4") (pinfunction "3D_4") (pintype "input"))
      (node (ref "IC35") (pin "4") (pinfunction "A3_4") (pintype "bidirectional"))
      (node (ref "IC41") (pin "12") (pinfunction "D8_12") (pintype "input"))
      (node (ref "IC6") (pin "16") (pinfunction "Y3_16") (pintype "tri_state"))
      (node (ref "P2") (pin "23") (pinfunction "KL_23") (pintype "passive"))
    )
    (net (code "130") (name "IBUS3") (class "Default")
      (node (ref "IC23") (pin "15") (pinfunction "Y4_15") (pintype "tri_state"))
      (node (ref "IC25") (pin "5") (pinfunction "4D_5") (pintype "input"))
      (node (ref "IC35") (pin "5") (pinfunction "A4_5") (pintype "bidirectional"))
      (node (ref "IC41") (pin "5") (pinfunction "D3_5") (pintype "input"))
      (node (ref "IC6") (pin "15") (pinfunction "Y4_15") (pintype "tri_state"))
      (node (ref "P2") (pin "24") (pinfunction "KL_24") (pintype "passive"))
    )
    (net (code "131") (name "IBUS4") (class "Default")
      (node (ref "IC23") (pin "14") (pinfunction "Y5_14") (pintype "tri_state"))
      (node (ref "IC25") (pin "6") (pinfunction "5D_6") (pintype "input"))
      (node (ref "IC35") (pin "6") (pinfunction "A5_6") (pintype "bidirectional"))
      (node (ref "IC41") (pin "9") (pinfunction "D7_9") (pintype "input"))
      (node (ref "IC6") (pin "14") (pinfunction "Y5_14") (pintype "tri_state"))
      (node (ref "P2") (pin "25") (pinfunction "KL_25") (pintype "passive"))
    )
    (net (code "132") (name "IBUS5") (class "Default")
      (node (ref "IC23") (pin "13") (pinfunction "Y6_13") (pintype "tri_state"))
      (node (ref "IC25") (pin "7") (pinfunction "6D_7") (pintype "input"))
      (node (ref "IC35") (pin "7") (pinfunction "A6_7") (pintype "bidirectional"))
      (node (ref "IC41") (pin "6") (pinfunction "D4_6") (pintype "input"))
      (node (ref "IC6") (pin "13") (pinfunction "Y6_13") (pintype "tri_state"))
      (node (ref "P2") (pin "26") (pinfunction "KL_26") (pintype "passive"))
    )
    (net (code "133") (name "IBUS6") (class "Default")
      (node (ref "IC23") (pin "12") (pinfunction "Y7_12") (pintype "tri_state"))
      (node (ref "IC25") (pin "8") (pinfunction "7D_8") (pintype "input"))
      (node (ref "IC35") (pin "8") (pinfunction "A7_8") (pintype "bidirectional"))
      (node (ref "IC41") (pin "8") (pinfunction "D6_8") (pintype "input"))
      (node (ref "IC6") (pin "12") (pinfunction "Y7_12") (pintype "tri_state"))
      (node (ref "P2") (pin "27") (pinfunction "KL_27") (pintype "passive"))
    )
    (net (code "134") (name "IBUS7") (class "Default")
      (node (ref "IC23") (pin "11") (pinfunction "Y8_11") (pintype "tri_state"))
      (node (ref "IC25") (pin "9") (pinfunction "8D_9") (pintype "input"))
      (node (ref "IC35") (pin "9") (pinfunction "A8_9") (pintype "bidirectional"))
      (node (ref "IC41") (pin "7") (pinfunction "D5_7") (pintype "input"))
      (node (ref "IC6") (pin "11") (pinfunction "Y8_11") (pintype "tri_state"))
      (node (ref "P2") (pin "28") (pinfunction "KL_28") (pintype "passive"))
    )
    (net (code "135") (name "IBUS8") (class "Default")
      (node (ref "IC24") (pin "18") (pinfunction "Y1_18") (pintype "tri_state"))
      (node (ref "IC26") (pin "2") (pinfunction "1D_2") (pintype "input"))
      (node (ref "IC36") (pin "2") (pinfunction "A1_2") (pintype "bidirectional"))
      (node (ref "IC42") (pin "1") (pinfunction "D1_1") (pintype "input"))
      (node (ref "IC7") (pin "18") (pinfunction "Y1_18") (pintype "tri_state"))
      (node (ref "P2") (pin "29") (pinfunction "KL_29") (pintype "passive"))
    )
    (net (code "136") (name "IBUS9") (class "Default")
      (node (ref "IC24") (pin "17") (pinfunction "Y2_17") (pintype "tri_state"))
      (node (ref "IC26") (pin "3") (pinfunction "2D_3") (pintype "input"))
      (node (ref "IC36") (pin "3") (pinfunction "A2_3") (pintype "bidirectional"))
      (node (ref "IC42") (pin "2") (pinfunction "D2_2") (pintype "input"))
      (node (ref "IC7") (pin "17") (pinfunction "Y2_17") (pintype "tri_state"))
      (node (ref "P2") (pin "30") (pinfunction "KL_30") (pintype "passive"))
    )
    (net (code "137") (name "IBUS10") (class "Default")
      (node (ref "IC24") (pin "16") (pinfunction "Y3_16") (pintype "tri_state"))
      (node (ref "IC26") (pin "4") (pinfunction "3D_4") (pintype "input"))
      (node (ref "IC36") (pin "4") (pinfunction "A3_4") (pintype "bidirectional"))
      (node (ref "IC42") (pin "12") (pinfunction "D8_12") (pintype "input"))
      (node (ref "IC7") (pin "16") (pinfunction "Y3_16") (pintype "tri_state"))
      (node (ref "P2") (pin "31") (pinfunction "KL_31") (pintype "passive"))
    )
    (net (code "138") (name "IBUS11") (class "Default")
      (node (ref "IC24") (pin "15") (pinfunction "Y4_15") (pintype "tri_state"))
      (node (ref "IC26") (pin "5") (pinfunction "4D_5") (pintype "input"))
      (node (ref "IC36") (pin "5") (pinfunction "A4_5") (pintype "bidirectional"))
      (node (ref "IC42") (pin "5") (pinfunction "D3_5") (pintype "input"))
      (node (ref "IC7") (pin "15") (pinfunction "Y4_15") (pintype "tri_state"))
      (node (ref "P2") (pin "32") (pinfunction "KL_32") (pintype "passive"))
    )
    (net (code "139") (name "IBUS12") (class "Default")
      (node (ref "IC24") (pin "14") (pinfunction "Y5_14") (pintype "tri_state"))
      (node (ref "IC26") (pin "6") (pinfunction "5D_6") (pintype "input"))
      (node (ref "IC36") (pin "6") (pinfunction "A5_6") (pintype "bidirectional"))
      (node (ref "IC42") (pin "9") (pinfunction "D7_9") (pintype "input"))
      (node (ref "IC7") (pin "14") (pinfunction "Y5_14") (pintype "tri_state"))
      (node (ref "P2") (pin "33") (pinfunction "KL_33") (pintype "passive"))
    )
    (net (code "140") (name "IBUS13") (class "Default")
      (node (ref "IC24") (pin "13") (pinfunction "Y6_13") (pintype "tri_state"))
      (node (ref "IC26") (pin "7") (pinfunction "6D_7") (pintype "input"))
      (node (ref "IC36") (pin "7") (pinfunction "A6_7") (pintype "bidirectional"))
      (node (ref "IC42") (pin "6") (pinfunction "D4_6") (pintype "input"))
      (node (ref "IC7") (pin "13") (pinfunction "Y6_13") (pintype "tri_state"))
      (node (ref "P2") (pin "34") (pinfunction "KL_34") (pintype "passive"))
    )
    (net (code "141") (name "IBUS14") (class "Default")
      (node (ref "IC24") (pin "12") (pinfunction "Y7_12") (pintype "tri_state"))
      (node (ref "IC26") (pin "8") (pinfunction "7D_8") (pintype "input"))
      (node (ref "IC36") (pin "8") (pinfunction "A7_8") (pintype "bidirectional"))
      (node (ref "IC42") (pin "8") (pinfunction "D6_8") (pintype "input"))
      (node (ref "IC7") (pin "12") (pinfunction "Y7_12") (pintype "tri_state"))
      (node (ref "P2") (pin "35") (pinfunction "KL_35") (pintype "passive"))
    )
    (net (code "142") (name "IBUS15") (class "Default")
      (node (ref "IC24") (pin "11") (pinfunction "Y8_11") (pintype "tri_state"))
      (node (ref "IC26") (pin "9") (pinfunction "8D_9") (pintype "input"))
      (node (ref "IC36") (pin "9") (pinfunction "A8_9") (pintype "bidirectional"))
      (node (ref "IC42") (pin "7") (pinfunction "D5_7") (pintype "input"))
      (node (ref "IC7") (pin "11") (pinfunction "Y8_11") (pintype "tri_state"))
      (node (ref "P2") (pin "36") (pinfunction "KL_36") (pintype "passive"))
    )
    (net (code "143") (name "IR0") (class "Default")
      (node (ref "IC13") (pin "1") (pinfunction "I0_1") (pintype "input"))
      (node (ref "IC16") (pin "2") (pinfunction "I1_2") (pintype "input"))
      (node (ref "IC23") (pin "2") (pinfunction "A1_2") (pintype "input"))
      (node (ref "IC25") (pin "19") (pinfunction "1Q_19") (pintype "tri_state"))
      (node (ref "IC8") (pin "2") (pinfunction "A1_2") (pintype "input"))
      (node (ref "P1") (pin "7") (pinfunction "KL_7") (pintype "passive"))
    )
    (net (code "144") (name "IR1") (class "Default")
      (node (ref "IC13") (pin "4") (pinfunction "I0_4") (pintype "input"))
      (node (ref "IC16") (pin "1") (pinfunction "I0_1") (pintype "input"))
      (node (ref "IC23") (pin "3") (pinfunction "A2_3") (pintype "input"))
      (node (ref "IC25") (pin "18") (pinfunction "2Q_18") (pintype "tri_state"))
      (node (ref "IC8") (pin "3") (pinfunction "A2_3") (pintype "input"))
    )
    (net (code "145") (name "IR2") (class "Default")
      (node (ref "IC13") (pin "9") (pinfunction "I0_9") (pintype "input"))
      (node (ref "IC16") (pin "5") (pinfunction "I1_5") (pintype "input"))
      (node (ref "IC23") (pin "4") (pinfunction "A3_4") (pintype "input"))
      (node (ref "IC25") (pin "17") (pinfunction "3Q_17") (pintype "tri_state"))
      (node (ref "IC8") (pin "4") (pinfunction "A3_4") (pintype "input"))
      (node (ref "P1") (pin "9") (pinfunction "KL_9") (pintype "passive"))
    )
    (net (code "146") (name "IR3") (class "Default")
      (node (ref "IC13") (pin "12") (pinfunction "I0_12") (pintype "input"))
      (node (ref "IC18") (pin "3") (pinfunction "I1_3") (pintype "input"))
      (node (ref "IC23") (pin "5") (pinfunction "A4_5") (pintype "input"))
      (node (ref "IC25") (pin "16") (pinfunction "4Q_16") (pintype "tri_state"))
      (node (ref "IC8") (pin "5") (pinfunction "A4_5") (pintype "input"))
    )
    (net (code "147") (name "IR4") (class "Default")
      (node (ref "IC15") (pin "1") (pinfunction "I0_1") (pintype "input"))
      (node (ref "IC18") (pin "2") (pinfunction "I2_2") (pintype "input"))
      (node (ref "IC23") (pin "6") (pinfunction "A5_6") (pintype "input"))
      (node (ref "IC25") (pin "15") (pinfunction "5Q_15") (pintype "tri_state"))
      (node (ref "IC8") (pin "6") (pinfunction "A5_6") (pintype "input"))
    )
    (net (code "148") (name "IR5") (class "Default")
      (node (ref "IC18") (pin "1") (pinfunction "I3_1") (pintype "input"))
      (node (ref "IC23") (pin "7") (pinfunction "A6_7") (pintype "input"))
      (node (ref "IC25") (pin "14") (pinfunction "6Q_14") (pintype "tri_state"))
      (node (ref "IC8") (pin "7") (pinfunction "A6_7") (pintype "input"))
    )
    (net (code "149") (name "IR6") (class "Default")
      (node (ref "IC18") (pin "15") (pinfunction "I4_15") (pintype "input"))
      (node (ref "IC23") (pin "8") (pinfunction "A7_8") (pintype "input"))
      (node (ref "IC25") (pin "13") (pinfunction "7Q_13") (pintype "tri_state"))
      (node (ref "IC8") (pin "8") (pinfunction "A7_8") (pintype "input"))
    )
    (net (code "150") (name "IR7") (class "Default")
      (node (ref "IC18") (pin "14") (pinfunction "I5_14") (pintype "input"))
      (node (ref "IC23") (pin "9") (pinfunction "A8_9") (pintype "input"))
      (node (ref "IC25") (pin "12") (pinfunction "8Q_12") (pintype "tri_state"))
      (node (ref "IC8") (pin "9") (pinfunction "A8_9") (pintype "input"))
    )
    (net (code "151") (name "IR8") (class "Default")
      (node (ref "IC18") (pin "13") (pinfunction "I6_13") (pintype "input"))
      (node (ref "IC24") (pin "2") (pinfunction "A1_2") (pintype "input"))
      (node (ref "IC26") (pin "19") (pinfunction "1Q_19") (pintype "tri_state"))
      (node (ref "IC27") (pin "2") (pinfunction "A1_2") (pintype "input"))
    )
    (net (code "152") (name "IR9") (class "Default")
      (node (ref "IC18") (pin "12") (pinfunction "I7_12") (pintype "input"))
      (node (ref "IC24") (pin "3") (pinfunction "A2_3") (pintype "input"))
      (node (ref "IC26") (pin "18") (pinfunction "2Q_18") (pintype "tri_state"))
      (node (ref "IC27") (pin "3") (pinfunction "A2_3") (pintype "input"))
    )
    (net (code "153") (name "IR10") (class "Default")
      (node (ref "IC22") (pin "1") (pinfunction "~{OE}_1") (pintype "input"))
      (node (ref "IC26") (pin "17") (pinfunction "3Q_17") (pintype "tri_state"))
      (node (ref "IC27") (pin "4") (pinfunction "A3_4") (pintype "input"))
    )
    (net (code "154") (name "IR11") (class "Default")
      (node (ref "IC26") (pin "16") (pinfunction "4Q_16") (pintype "tri_state"))
      (node (ref "IC27") (pin "5") (pinfunction "A4_5") (pintype "input"))
      (node (ref "P1") (pin "22") (pinfunction "KL_22") (pintype "passive"))
    )
    (net (code "155") (name "IR12") (class "Default")
      (node (ref "IC26") (pin "15") (pinfunction "5Q_15") (pintype "tri_state"))
      (node (ref "IC27") (pin "6") (pinfunction "A5_6") (pintype "input"))
      (node (ref "P2") (pin "37") (pinfunction "KL_37") (pintype "passive"))
    )
    (net (code "156") (name "IR13") (class "Default")
      (node (ref "IC26") (pin "14") (pinfunction "6Q_14") (pintype "tri_state"))
      (node (ref "IC27") (pin "7") (pinfunction "A6_7") (pintype "input"))
      (node (ref "P2") (pin "38") (pinfunction "KL_38") (pintype "passive"))
    )
    (net (code "157") (name "IR14") (class "Default")
      (node (ref "IC26") (pin "13") (pinfunction "7Q_13") (pintype "tri_state"))
      (node (ref "IC27") (pin "8") (pinfunction "A7_8") (pintype "input"))
      (node (ref "P2") (pin "39") (pinfunction "KL_39") (pintype "passive"))
    )
    (net (code "158") (name "IR15") (class "Default")
      (node (ref "IC26") (pin "12") (pinfunction "8Q_12") (pintype "tri_state"))
      (node (ref "IC27") (pin "9") (pinfunction "A8_9") (pintype "input"))
      (node (ref "P2") (pin "40") (pinfunction "KL_40") (pintype "passive"))
    )
    (net (code "159") (name "LATCH-IR") (class "Default")
      (node (ref "IC25") (pin "11") (pinfunction "LE_11") (pintype "input"))
      (node (ref "IC26") (pin "11") (pinfunction "LE_11") (pintype "input"))
      (node (ref "R11") (pin "2") (pinfunction "2_2") (pintype "passive"))
    )
    (net (code "160") (name "Net-(IC1A-1C2)") (class "Default")
      (node (ref "IC1") (pin "3") (pinfunction "1C3_3") (pintype "input"))
      (node (ref "IC1") (pin "4") (pinfunction "1C2_4") (pintype "input"))
      (node (ref "XTAL1") (pin "5") (pinfunction "OUT_5") (pintype "output"))
    )
    (net (code "161") (name "Net-(IC1A-1Y)") (class "Default")
      (node (ref "IC1") (pin "7") (pinfunction "1Y_7") (pintype "tri_state"))
      (node (ref "IC2") (pin "5") (pinfunction "UP_5") (pintype "input"))
    )
    (net (code "162") (name "Net-(IC4A-I)") (class "Default")
      (node (ref "C13") (pin "2") (pinfunction "2_2") (pintype "passive"))
      (node (ref "IC4") (pin "2") (pinfunction "I_2") (pintype "input"))
      (node (ref "JP1") (pin "2") (pinfunction "2_2") (pintype "passive"))
      (node (ref "R9") (pin "1") (pinfunction "1_1") (pintype "passive"))
      (node (ref "S1") (pin "3") (pinfunction "3_3") (pintype "passive"))
      (node (ref "S1") (pin "4") (pinfunction "4_4") (pintype "passive"))
    )
    (net (code "163") (name "Net-(IC4A-O)") (class "Default")
      (node (ref "D3") (pin "C") (pinfunction "C_C") (pintype "passive"))
      (node (ref "IC4") (pin "4") (pinfunction "O_4") (pintype "output"))
    )
    (net (code "164") (name "Net-(IC5A-QD)") (class "Default")
      (node (ref "IC5") (pin "3") (pinfunction "QD_3") (pintype "tri_state"))
      (node (ref "JP2") (pin "1") (pinfunction "1_1") (pintype "passive"))
    )
    (net (code "165") (name "Net-(IC5A-QE)") (class "Default")
      (node (ref "IC5") (pin "4") (pinfunction "QE_4") (pintype "tri_state"))
      (node (ref "JP2") (pin "3") (pinfunction "3_3") (pintype "passive"))
    )
    (net (code "166") (name "Net-(IC5A-QF)") (class "Default")
      (node (ref "IC5") (pin "5") (pinfunction "QF_5") (pintype "tri_state"))
      (node (ref "JP2") (pin "5") (pinfunction "5_5") (pintype "passive"))
    )
    (net (code "167") (name "Net-(IC5A-QG)") (class "Default")
      (node (ref "IC5") (pin "6") (pinfunction "QG_6") (pintype "tri_state"))
      (node (ref "JP2") (pin "7") (pinfunction "7_7") (pintype "passive"))
    )
    (net (code "168") (name "Net-(IC5A-QH)") (class "Default")
      (node (ref "IC5") (pin "7") (pinfunction "QH_7") (pintype "tri_state"))
      (node (ref "JP2") (pin "9") (pinfunction "9_9") (pintype "passive"))
    )
    (net (code "169") (name "Net-(IC9A-I)") (class "Default")
      (node (ref "IC9") (pin "1") (pinfunction "I_1") (pintype "input"))
      (node (ref "IC9") (pin "12") (pinfunction "O_12") (pintype "output"))
    )
    (net (code "170") (name "Net-(IC9B-I)") (class "Default")
      (node (ref "IC9") (pin "10") (pinfunction "O_10") (pintype "output"))
      (node (ref "IC9") (pin "3") (pinfunction "I_3") (pintype "input"))
    )
    (net (code "171") (name "Net-(IC9C-I)") (class "Default")
      (node (ref "IC9") (pin "5") (pinfunction "I_5") (pintype "input"))
      (node (ref "IC9") (pin "8") (pinfunction "O_8") (pintype "output"))
    )
    (net (code "172") (name "Net-(IC10A-I)") (class "Default")
      (node (ref "IC10") (pin "2") (pinfunction "I_2") (pintype "input"))
      (node (ref "IC40") (pin "6") (pinfunction "~{Q}_6") (pintype "output"))
    )
    (net (code "173") (name "Net-(IC10A-O)") (class "Default")
      (node (ref "IC10") (pin "4") (pinfunction "O_4") (pintype "tri_state"))
      (node (ref "SJ1") (pin "3") (pinfunction "3_3") (pintype "passive"))
    )
    (net (code "174") (name "Net-(IC11A-O)") (class "Default")
      (node (ref "IC11") (pin "4") (pinfunction "O_4") (pintype "output"))
      (node (ref "R11") (pin "1") (pinfunction "1_1") (pintype "passive"))
    )
    (net (code "175") (name "Net-(IC12A-D)") (class "Default")
      (node (ref "IC12") (pin "2") (pinfunction "D_2") (pintype "input"))
      (node (ref "IC12") (pin "9") (pinfunction "Q_9") (pintype "output"))
    )
    (net (code "176") (name "Net-(IC16A-O)") (class "Default")
      (node (ref "IC16") (pin "3") (pinfunction "O_3") (pintype "output"))
      (node (ref "IC16") (pin "4") (pinfunction "I0_4") (pintype "input"))
    )
    (net (code "177") (name "Net-(IC21A-Q)") (class "Default")
      (node (ref "IC21") (pin "5") (pinfunction "Q_5") (pintype "output"))
      (node (ref "R41") (pin "2") (pinfunction "2_2") (pintype "passive"))
    )
    (net (code "178") (name "Net-(IC21B-Q)") (class "Default")
      (node (ref "IC21") (pin "9") (pinfunction "Q_9") (pintype "output"))
      (node (ref "R50") (pin "2") (pinfunction "2_2") (pintype "passive"))
    )
    (net (code "179") (name "Net-(IC32A-O)") (class "Default")
      (node (ref "IC32") (pin "4") (pinfunction "O_4") (pintype "output"))
      (node (ref "IC33") (pin "4") (pinfunction "PRE_4") (pintype "input"))
    )
    (net (code "180") (name "Net-(IC37A-O)") (class "Default")
      (node (ref "IC37") (pin "13") (pinfunction "I_13") (pintype "input"))
      (node (ref "IC37") (pin "2") (pinfunction "O_2") (pintype "output"))
    )
    (net (code "181") (name "Net-(IC37B-I)") (class "Default")
      (node (ref "IC37") (pin "3") (pinfunction "I_3") (pintype "input"))
      (node (ref "IC37") (pin "8") (pinfunction "O_8") (pintype "output"))
    )
    (net (code "182") (name "Net-(IC37B-O)") (class "Default")
      (node (ref "IC37") (pin "4") (pinfunction "O_4") (pintype "output"))
      (node (ref "JP3") (pin "7") (pinfunction "7_7") (pintype "passive"))
    )
    (net (code "183") (name "Net-(IC37C-I)") (class "Default")
      (node (ref "IC37") (pin "10") (pinfunction "O_10") (pintype "output"))
      (node (ref "IC37") (pin "5") (pinfunction "I_5") (pintype "input"))
    )
    (net (code "184") (name "Net-(IC37C-O)") (class "Default")
      (node (ref "IC37") (pin "6") (pinfunction "O_6") (pintype "output"))
      (node (ref "IC37") (pin "9") (pinfunction "I_9") (pintype "input"))
      (node (ref "JP3") (pin "5") (pinfunction "5_5") (pintype "passive"))
    )
    (net (code "185") (name "Net-(IC37E-I)") (class "Default")
      (node (ref "IC37") (pin "11") (pinfunction "I_11") (pintype "input"))
      (node (ref "IC37") (pin "12") (pinfunction "O_12") (pintype "output"))
      (node (ref "JP3") (pin "3") (pinfunction "3_3") (pintype "passive"))
    )
    (net (code "186") (name "Net-(IC38A-O)") (class "Default")
      (node (ref "IC38") (pin "4") (pinfunction "O_4") (pintype "output"))
      (node (ref "IC40") (pin "11") (pinfunction "CLK_11") (pintype "input"))
      (node (ref "IC40") (pin "3") (pinfunction "CLK_3") (pintype "input"))
      (node (ref "SJ1") (pin "1") (pinfunction "1_1") (pintype "passive"))
    )
    (net (code "187") (name "Net-(IC39B-I0)") (class "Default")
      (node (ref "IC39") (pin "1") (pinfunction "I0_1") (pintype "input"))
      (node (ref "JP3") (pin "2") (pinfunction "2_2") (pintype "passive"))
      (node (ref "JP3") (pin "4") (pinfunction "4_4") (pintype "passive"))
      (node (ref "JP3") (pin "6") (pinfunction "6_6") (pintype "passive"))
      (node (ref "JP3") (pin "8") (pinfunction "8_8") (pintype "passive"))
      (node (ref "R5") (pin "1") (pinfunction "1_1") (pintype "passive"))
    )
    (net (code "188") (name "Net-(IC39B-O)") (class "Default")
      (node (ref "IC39") (pin "4") (pinfunction "O_4") (pintype "output"))
      (node (ref "IC40") (pin "1") (pinfunction "CLR_1") (pintype "input"))
      (node (ref "IC40") (pin "13") (pinfunction "CLR_13") (pintype "input"))
    )
    (net (code "189") (name "Net-(LED1-PadA)") (class "Default")
      (node (ref "LED1") (pin "A") (pinfunction "A_A") (pintype "passive"))
      (node (ref "R3") (pin "2") (pinfunction "2_2") (pintype "passive"))
    )
    (net (code "190") (name "Net-(LED2-PadA)") (class "Default")
      (node (ref "LED2") (pin "A") (pinfunction "A_A") (pintype "passive"))
      (node (ref "R8") (pin "1") (pinfunction "1_1") (pintype "passive"))
    )
    (net (code "191") (name "Net-(LED3-PadA)") (class "Default")
      (node (ref "LED3") (pin "A") (pinfunction "A_A") (pintype "passive"))
      (node (ref "R49") (pin "1") (pinfunction "1_1") (pintype "passive"))
    )
    (net (code "192") (name "Net-(LED4-PadA)") (class "Default")
      (node (ref "LED4") (pin "A") (pinfunction "A_A") (pintype "passive"))
      (node (ref "R50") (pin "1") (pinfunction "1_1") (pintype "passive"))
    )
    (net (code "193") (name "Net-(R51-Pad2)") (class "Default")
      (node (ref "R51") (pin "2") (pinfunction "2_2") (pintype "passive"))
      (node (ref "SJ1") (pin "2") (pinfunction "2_2") (pintype "passive"))
    )
    (net (code "194") (name "Net-(T1-B)") (class "Default")
      (node (ref "R15") (pin "1") (pinfunction "1_1") (pintype "passive"))
      (node (ref "T1") (pin "1") (pinfunction "B_1") (pintype "passive"))
    )
    (net (code "195") (name "Net-(T1-C)") (class "Default")
      (node (ref "LED1") (pin "C") (pinfunction "C_C") (pintype "passive"))
      (node (ref "T1") (pin "3") (pinfunction "C_3") (pintype "passive"))
    )
    (net (code "196") (name "Net-(T2-B)") (class "Default")
      (node (ref "R10") (pin "1") (pinfunction "1_1") (pintype "passive"))
      (node (ref "T2") (pin "1") (pinfunction "B_1") (pintype "passive"))
    )
    (net (code "197") (name "Net-(T2-C)") (class "Default")
      (node (ref "R8") (pin "2") (pinfunction "2_2") (pintype "passive"))
      (node (ref "T2") (pin "3") (pinfunction "C_3") (pintype "passive"))
    )
    (net (code "198") (name "OP1_BRANCH") (class "Default")
      (node (ref "IC15") (pin "4") (pinfunction "O_4") (pintype "output"))
      (node (ref "IC19") (pin "12") (pinfunction "I7_12") (pintype "input"))
    )
    (net (code "199") (name "OP2_ROLL") (class "Default")
      (node (ref "IC16") (pin "6") (pinfunction "O_6") (pintype "output"))
      (node (ref "IC19") (pin "13") (pinfunction "I6_13") (pintype "input"))
    )
    (net (code "200") (name "OPIF0") (class "Default")
      (node (ref "IC18") (pin "11") (pinfunction "S0_11") (pintype "input"))
      (node (ref "IC19") (pin "11") (pinfunction "S0_11") (pintype "input"))
      (node (ref "P1") (pin "18") (pinfunction "KL_18") (pintype "passive"))
    )
    (net (code "201") (name "OPIF1") (class "Default")
      (node (ref "IC18") (pin "10") (pinfunction "S1_10") (pintype "input"))
      (node (ref "IC19") (pin "10") (pinfunction "S1_10") (pintype "input"))
      (node (ref "P1") (pin "19") (pinfunction "KL_19") (pintype "passive"))
    )
    (net (code "202") (name "OPIF2") (class "Default")
      (node (ref "IC18") (pin "9") (pinfunction "S2_9") (pintype "input"))
      (node (ref "IC19") (pin "9") (pinfunction "S2_9") (pintype "input"))
      (node (ref "P1") (pin "20") (pinfunction "KL_20") (pintype "passive"))
    )
    (net (code "203") (name "OPIF3") (class "Default")
      (node (ref "IC17") (pin "2") (pinfunction "I_2") (pintype "input"))
      (node (ref "IC18") (pin "7") (pinfunction "~{OE}_7") (pintype "input"))
      (node (ref "P1") (pin "21") (pinfunction "KL_21") (pintype "passive"))
    )
    (net (code "204") (name "PAGE0") (class "Default")
      (node (ref "IC22") (pin "19") (pinfunction "1Q_19") (pintype "tri_state"))
      (node (ref "IC24") (pin "4") (pinfunction "A3_4") (pintype "input"))
      (node (ref "RN1") (pin "8") (pinfunction "8_8") (pintype "passive"))
    )
    (net (code "205") (name "PAGE1") (class "Default")
      (node (ref "IC22") (pin "18") (pinfunction "2Q_18") (pintype "tri_state"))
      (node (ref "IC24") (pin "5") (pinfunction "A4_5") (pintype "input"))
      (node (ref "RN1") (pin "7") (pinfunction "7_7") (pintype "passive"))
    )
    (net (code "206") (name "PAGE2") (class "Default")
      (node (ref "IC22") (pin "17") (pinfunction "3Q_17") (pintype "tri_state"))
      (node (ref "IC24") (pin "6") (pinfunction "A5_6") (pintype "input"))
      (node (ref "RN1") (pin "6") (pinfunction "6_6") (pintype "passive"))
    )
    (net (code "207") (name "PAGE3") (class "Default")
      (node (ref "IC22") (pin "16") (pinfunction "4Q_16") (pintype "tri_state"))
      (node (ref "IC24") (pin "7") (pinfunction "A6_7") (pintype "input"))
      (node (ref "RN1") (pin "5") (pinfunction "5_5") (pintype "passive"))
    )
    (net (code "208") (name "PAGE4") (class "Default")
      (node (ref "IC22") (pin "15") (pinfunction "5Q_15") (pintype "tri_state"))
      (node (ref "IC24") (pin "8") (pinfunction "A7_8") (pintype "input"))
      (node (ref "RN19") (pin "8") (pinfunction "8_8") (pintype "passive"))
    )
    (net (code "209") (name "PAGE5") (class "Default")
      (node (ref "IC22") (pin "14") (pinfunction "6Q_14") (pintype "tri_state"))
      (node (ref "IC24") (pin "9") (pinfunction "A8_9") (pintype "input"))
      (node (ref "RN19") (pin "7") (pinfunction "7_7") (pintype "passive"))
    )
    (net (code "210") (name "PC10") (class "Default")
      (node (ref "IC22") (pin "2") (pinfunction "1D_2") (pintype "input"))
      (node (ref "P2") (pin "13") (pinfunction "KL_13") (pintype "passive"))
    )
    (net (code "211") (name "PC11") (class "Default")
      (node (ref "IC22") (pin "3") (pinfunction "2D_3") (pintype "input"))
      (node (ref "P2") (pin "14") (pinfunction "KL_14") (pintype "passive"))
    )
    (net (code "212") (name "PC12") (class "Default")
      (node (ref "IC22") (pin "4") (pinfunction "3D_4") (pintype "input"))
      (node (ref "P2") (pin "15") (pinfunction "KL_15") (pintype "passive"))
    )
    (net (code "213") (name "PC13") (class "Default")
      (node (ref "IC22") (pin "5") (pinfunction "4D_5") (pintype "input"))
      (node (ref "P2") (pin "16") (pinfunction "KL_16") (pintype "passive"))
    )
    (net (code "214") (name "PC14") (class "Default")
      (node (ref "IC22") (pin "6") (pinfunction "5D_6") (pintype "input"))
      (node (ref "P2") (pin "17") (pinfunction "KL_17") (pintype "passive"))
    )
    (net (code "215") (name "PC15") (class "Default")
      (node (ref "IC22") (pin "7") (pinfunction "6D_7") (pintype "input"))
      (node (ref "P2") (pin "18") (pinfunction "KL_18") (pintype "passive"))
    )
    (net (code "216") (name "POWEROK") (class "Default")
      (node (ref "D2") (pin "C") (pinfunction "C_C") (pintype "passive"))
      (node (ref "P3") (pin "30") (pinfunction "KL_30") (pintype "passive"))
      (node (ref "R10") (pin "2") (pinfunction "2_2") (pintype "passive"))
    )
    (net (code "217") (name "RUNIT0") (class "Default")
      (node (ref "P1") (pin "11") (pinfunction "KL_11") (pintype "passive"))
    )
    (net (code "218") (name "RUNIT1") (class "Default")
      (node (ref "P1") (pin "12") (pinfunction "KL_12") (pintype "passive"))
    )
    (net (code "219") (name "RUNIT2") (class "Default")
      (node (ref "P1") (pin "13") (pinfunction "KL_13") (pintype "passive"))
    )
    (net (code "220") (name "RUNIT3") (class "Default")
      (node (ref "P1") (pin "14") (pinfunction "KL_14") (pintype "passive"))
    )
    (net (code "221") (name "SKIPMUXHI") (class "Default")
      (node (ref "IC19") (pin "5") (pinfunction "Y_5") (pintype "tri_state"))
      (node (ref "IC20") (pin "1") (pinfunction "I0_1") (pintype "input"))
      (node (ref "R7") (pin "2") (pinfunction "2_2") (pintype "passive"))
    )
    (net (code "222") (name "SKIPMUXLO") (class "Default")
      (node (ref "IC18") (pin "5") (pinfunction "Y_5") (pintype "tri_state"))
      (node (ref "IC20") (pin "6") (pinfunction "I2_6") (pintype "input"))
      (node (ref "R6") (pin "2") (pinfunction "2_2") (pintype "passive"))
    )
    (net (code "223") (name "SL") (class "Default")
      (node (ref "IC13") (pin "6") (pinfunction "O_6") (pintype "output"))
      (node (ref "IC14") (pin "1") (pinfunction "I0_1") (pintype "input"))
    )
    (net (code "224") (name "SN") (class "Default")
      (node (ref "IC13") (pin "11") (pinfunction "O_11") (pintype "output"))
      (node (ref "IC14") (pin "4") (pinfunction "I0_4") (pintype "input"))
    )
    (net (code "225") (name "SV") (class "Default")
      (node (ref "IC13") (pin "3") (pinfunction "O_3") (pintype "output"))
      (node (ref "IC14") (pin "2") (pinfunction "I1_2") (pintype "input"))
    )
    (net (code "226") (name "SVL") (class "Default")
      (node (ref "IC14") (pin "10") (pinfunction "I1_10") (pintype "input"))
      (node (ref "IC14") (pin "3") (pinfunction "O_3") (pintype "output"))
    )
    (net (code "227") (name "SVLZN") (class "Default")
      (node (ref "IC14") (pin "8") (pinfunction "O_8") (pintype "output"))
      (node (ref "IC15") (pin "2") (pinfunction "I1_2") (pintype "input"))
    )
    (net (code "228") (name "SZ") (class "Default")
      (node (ref "IC13") (pin "8") (pinfunction "O_8") (pintype "output"))
      (node (ref "IC14") (pin "5") (pinfunction "I1_5") (pintype "input"))
    )
    (net (code "229") (name "SZN") (class "Default")
      (node (ref "IC14") (pin "6") (pinfunction "O_6") (pintype "output"))
      (node (ref "IC14") (pin "9") (pinfunction "I0_9") (pintype "input"))
    )
    (net (code "230") (name "VCC") (class "Default")
      (node (ref "C1") (pin "2") (pinfunction "2_2") (pintype "passive"))
      (node (ref "C10") (pin "+") (pinfunction "+_+") (pintype "passive"))
      (node (ref "C11") (pin "2") (pinfunction "2_2") (pintype "passive"))
      (node (ref "C12") (pin "2") (pinfunction "2_2") (pintype "passive"))
      (node (ref "C14") (pin "+") (pinfunction "+_+") (pintype "passive"))
      (node (ref "C15") (pin "2") (pinfunction "2_2") (pintype "passive"))
      (node (ref "C16") (pin "2") (pinfunction "2_2") (pintype "passive"))
      (node (ref "C2") (pin "2") (pinfunction "2_2") (pintype "passive"))
      (node (ref "C21") (pin "2") (pinfunction "2_2") (pintype "passive"))
      (node (ref "C22") (pin "2") (pinfunction "2_2") (pintype "passive"))
      (node (ref "C23") (pin "2") (pinfunction "2_2") (pintype "passive"))
      (node (ref "C24") (pin "2") (pinfunction "2_2") (pintype "passive"))
      (node (ref "C25") (pin "2") (pinfunction "2_2") (pintype "passive"))
      (node (ref "C26") (pin "2") (pinfunction "2_2") (pintype "passive"))
      (node (ref "C27") (pin "2") (pinfunction "2_2") (pintype "passive"))
      (node (ref "C28") (pin "2") (pinfunction "2_2") (pintype "passive"))
      (node (ref "C29") (pin "2") (pinfunction "2_2") (pintype "passive"))
      (node (ref "C3") (pin "2") (pinfunction "2_2") (pintype "passive"))
      (node (ref "C30") (pin "2") (pinfunction "2_2") (pintype "passive"))
      (node (ref "C31") (pin "2") (pinfunction "2_2") (pintype "passive"))
      (node (ref "C32") (pin "2") (pinfunction "2_2") (pintype "passive"))
      (node (ref "C33") (pin "2") (pinfunction "2_2") (pintype "passive"))
      (node (ref "C34") (pin "2") (pinfunction "2_2") (pintype "passive"))
      (node (ref "C35") (pin "2") (pinfunction "2_2") (pintype "passive"))
      (node (ref "C36") (pin "2") (pinfunction "2_2") (pintype "passive"))
      (node (ref "C37") (pin "2") (pinfunction "2_2") (pintype "passive"))
      (node (ref "C38") (pin "2") (pinfunction "2_2") (pintype "passive"))
      (node (ref "C39") (pin "2") (pinfunction "2_2") (pintype "passive"))
      (node (ref "C4") (pin "2") (pinfunction "2_2") (pintype "passive"))
      (node (ref "C40") (pin "2") (pinfunction "2_2") (pintype "passive"))
      (node (ref "C44") (pin "2") (pinfunction "2_2") (pintype "passive"))
      (node (ref "C45") (pin "2") (pinfunction "2_2") (pintype "passive"))
      (node (ref "C46") (pin "2") (pinfunction "2_2") (pintype "passive"))
      (node (ref "C47") (pin "2") (pinfunction "2_2") (pintype "passive"))
      (node (ref "C48") (pin "2") (pinfunction "2_2") (pintype "passive"))
      (node (ref "C49") (pin "2") (pinfunction "2_2") (pintype "passive"))
      (node (ref "C5") (pin "2") (pinfunction "2_2") (pintype "passive"))
      (node (ref "C50") (pin "2") (pinfunction "2_2") (pintype "passive"))
      (node (ref "C51") (pin "2") (pinfunction "2_2") (pintype "passive"))
      (node (ref "C52") (pin "2") (pinfunction "2_2") (pintype "passive"))
      (node (ref "C53") (pin "2") (pinfunction "2_2") (pintype "passive"))
      (node (ref "C54") (pin "2") (pinfunction "2_2") (pintype "passive"))
      (node (ref "C55") (pin "2") (pinfunction "2_2") (pintype "passive"))
      (node (ref "C56") (pin "2") (pinfunction "2_2") (pintype "passive"))
      (node (ref "C57") (pin "+") (pinfunction "+_+") (pintype "passive"))
      (node (ref "C6") (pin "2") (pinfunction "2_2") (pintype "passive"))
      (node (ref "C7") (pin "2") (pinfunction "2_2") (pintype "passive"))
      (node (ref "C8") (pin "2") (pinfunction "2_2") (pintype "passive"))
      (node (ref "C9") (pin "2") (pinfunction "2_2") (pintype "passive"))
      (node (ref "EXP1") (pin "A3") (pinfunction "3_A3") (pintype "passive"))
      (node (ref "EXP1") (pin "A32") (pinfunction "32_A32") (pintype "passive"))
      (node (ref "EXP1") (pin "B3") (pinfunction "3_B3") (pintype "passive"))
      (node (ref "EXP1") (pin "B32") (pinfunction "32_B32") (pintype "passive"))
      (node (ref "EXP1") (pin "C3") (pinfunction "3_C3") (pintype "passive"))
      (node (ref "EXP1") (pin "C32") (pinfunction "32_C32") (pintype "passive"))
      (node (ref "IC1") (pin "5") (pinfunction "1C1_5") (pintype "input"))
      (node (ref "IC12") (pin "4") (pinfunction "PRE_4") (pintype "input"))
      (node (ref "IC16") (pin "10") (pinfunction "I1_10") (pintype "input"))
      (node (ref "IC16") (pin "12") (pinfunction "I0_12") (pintype "input"))
      (node (ref "IC16") (pin "13") (pinfunction "I1_13") (pintype "input"))
      (node (ref "IC16") (pin "9") (pinfunction "I0_9") (pintype "input"))
      (node (ref "IC2") (pin "4") (pinfunction "DOWN_4") (pintype "input"))
      (node (ref "IC21") (pin "1") (pinfunction "CLR_1") (pintype "input"))
      (node (ref "IC21") (pin "10") (pinfunction "PRE_10") (pintype "input"))
      (node (ref "IC39") (pin "6") (pinfunction "I2_6") (pintype "input"))
      (node (ref "IC40") (pin "10") (pinfunction "PRE_10") (pintype "input"))
      (node (ref "IC40") (pin "12") (pinfunction "D_12") (pintype "input"))
      (node (ref "IC40") (pin "2") (pinfunction "D_2") (pintype "input"))
      (node (ref "IC40") (pin "4") (pinfunction "PRE_4") (pintype "input"))
      (node (ref "IC6") (pin "6") (pinfunction "A5_6") (pintype "input"))
      (node (ref "IC6") (pin "7") (pinfunction "A6_7") (pintype "input"))
      (node (ref "IC6") (pin "8") (pinfunction "A7_8") (pintype "input"))
      (node (ref "IC6") (pin "9") (pinfunction "A8_9") (pintype "input"))
      (node (ref "IC7") (pin "2") (pinfunction "A1_2") (pintype "input"))
      (node (ref "IC7") (pin "3") (pinfunction "A2_3") (pintype "input"))
      (node (ref "IC7") (pin "4") (pinfunction "A3_4") (pintype "input"))
      (node (ref "IC7") (pin "5") (pinfunction "A4_5") (pintype "input"))
      (node (ref "IC7") (pin "6") (pinfunction "A5_6") (pintype "input"))
      (node (ref "IC7") (pin "7") (pinfunction "A6_7") (pintype "input"))
      (node (ref "IC7") (pin "8") (pinfunction "A7_8") (pintype "input"))
      (node (ref "IC7") (pin "9") (pinfunction "A8_9") (pintype "input"))
      (node (ref "LED2") (pin "C") (pinfunction "C_C") (pintype "passive"))
      (node (ref "R1") (pin "2") (pinfunction "2_2") (pintype "passive"))
      (node (ref "R13") (pin "2") (pinfunction "2_2") (pintype "passive"))
      (node (ref "R3") (pin "1") (pinfunction "1_1") (pintype "passive"))
      (node (ref "R40") (pin "1") (pinfunction "1_1") (pintype "passive"))
      (node (ref "R48") (pin "2") (pinfunction "2_2") (pintype "passive"))
      (node (ref "R6") (pin "1") (pinfunction "1_1") (pintype "passive"))
      (node (ref "R7") (pin "1") (pinfunction "1_1") (pintype "passive"))
      (node (ref "R9") (pin "2") (pinfunction "2_2") (pintype "passive"))
      (node (ref "XTAL1") (pin "8") (pinfunction "VCC_8") (pintype "power_in"))
    )
    (net (code "231") (name "WAITING") (class "Default")
      (node (ref "IC33") (pin "5") (pinfunction "Q_5") (pintype "output"))
      (node (ref "IC38") (pin "3") (pinfunction "I2_3") (pintype "input"))
    )
    (net (code "232") (name "unconnected-(EXP1B-5-PadB5)") (class "Default")
      (node (ref "EXP1") (pin "B5") (pinfunction "5_B5") (pintype "passive"))
    )
    (net (code "233") (name "unconnected-(EXP1B-21-PadB21)") (class "Default")
      (node (ref "EXP1") (pin "B21") (pinfunction "21_B21") (pintype "passive"))
    )
    (net (code "234") (name "unconnected-(EXP1B-23-PadB23)") (class "Default")
      (node (ref "EXP1") (pin "B23") (pinfunction "23_B23") (pintype "passive"))
    )
    (net (code "235") (name "unconnected-(IC1A-2Y-Pad9)") (class "Default")
      (node (ref "IC1") (pin "9") (pinfunction "2Y_9") (pintype "tri_state"))
    )
    (net (code "236") (name "unconnected-(IC2A-BORROW-Pad13)") (class "Default")
      (node (ref "IC2") (pin "13") (pinfunction "BORROW_13") (pintype "output"))
    )
    (net (code "237") (name "unconnected-(IC2A-CARRY-Pad12)") (class "Default")
      (node (ref "IC2") (pin "12") (pinfunction "CARRY_12") (pintype "output"))
    )
    (net (code "238") (name "unconnected-(IC2A-QC-Pad6)") (class "Default")
      (node (ref "IC2") (pin "6") (pinfunction "QC_6") (pintype "output"))
    )
    (net (code "239") (name "unconnected-(IC2A-QD-Pad7)") (class "Default")
      (node (ref "IC2") (pin "7") (pinfunction "QD_7") (pintype "output"))
    )
    (net (code "240") (name "unconnected-(IC3B-Y0-Pad12)") (class "Default")
      (node (ref "IC3") (pin "12") (pinfunction "Y0_12") (pintype "output"))
    )
    (net (code "241") (name "unconnected-(IC3B-Y2-Pad10)") (class "Default")
      (node (ref "IC3") (pin "10") (pinfunction "Y2_10") (pintype "output"))
    )
    (net (code "242") (name "unconnected-(IC3B-Y3-Pad9)") (class "Default")
      (node (ref "IC3") (pin "9") (pinfunction "Y3_9") (pintype "output"))
    )
    (net (code "243") (name "unconnected-(IC5A-QA-Pad15)") (class "Default")
      (node (ref "IC5") (pin "15") (pinfunction "QA_15") (pintype "tri_state"))
    )
    (net (code "244") (name "unconnected-(IC5A-QB-Pad1)") (class "Default")
      (node (ref "IC5") (pin "1") (pinfunction "QB_1") (pintype "tri_state"))
    )
    (net (code "245") (name "unconnected-(IC5A-QC-Pad2)") (class "Default")
      (node (ref "IC5") (pin "2") (pinfunction "QC_2") (pintype "tri_state"))
    )
    (net (code "246") (name "unconnected-(IC5A-RCO-Pad9)") (class "Default")
      (node (ref "IC5") (pin "9") (pinfunction "RCO_9") (pintype "output"))
    )
    (net (code "247") (name "unconnected-(IC12A-Q-Pad5)") (class "Default")
      (node (ref "IC12") (pin "5") (pinfunction "Q_5") (pintype "output"))
    )
    (net (code "248") (name "unconnected-(IC12B-~{Q}-Pad8)") (class "Default")
      (node (ref "IC12") (pin "8") (pinfunction "~{Q}_8") (pintype "output"))
    )
    (net (code "249") (name "unconnected-(IC14D-O-Pad11)") (class "Default")
      (node (ref "IC14") (pin "11") (pinfunction "O_11") (pintype "output"))
    )
    (net (code "250") (name "unconnected-(IC16C-O-Pad8)") (class "Default")
      (node (ref "IC16") (pin "8") (pinfunction "O_8") (pintype "output"))
    )
    (net (code "251") (name "unconnected-(IC16D-O-Pad11)") (class "Default")
      (node (ref "IC16") (pin "11") (pinfunction "O_11") (pintype "output"))
    )
    (net (code "252") (name "unconnected-(IC18A-~{Y}-Pad6)") (class "Default")
      (node (ref "IC18") (pin "6") (pinfunction "~{Y}_6") (pintype "tri_state"))
    )
    (net (code "253") (name "unconnected-(IC19A-~{Y}-Pad6)") (class "Default")
      (node (ref "IC19") (pin "6") (pinfunction "~{Y}_6") (pintype "tri_state"))
    )
    (net (code "254") (name "unconnected-(IC21A-~{Q}-Pad6)") (class "Default")
      (node (ref "IC21") (pin "6") (pinfunction "~{Q}_6") (pintype "output"))
    )
    (net (code "255") (name "unconnected-(IC22A-7Q-Pad13)") (class "Default")
      (node (ref "IC22") (pin "13") (pinfunction "7Q_13") (pintype "tri_state"))
    )
    (net (code "256") (name "unconnected-(IC22A-8Q-Pad12)") (class "Default")
      (node (ref "IC22") (pin "12") (pinfunction "8Q_12") (pintype "tri_state"))
    )
    (net (code "257") (name "unconnected-(IC31B-~{Q}-Pad7)") (class "Default")
      (node (ref "IC31") (pin "7") (pinfunction "~{Q}_7") (pintype "output"))
    )
    (net (code "258") (name "unconnected-(IC33B-Q-Pad9)") (class "Default")
      (node (ref "IC33") (pin "9") (pinfunction "Q_9") (pintype "output"))
    )
    (net (code "259") (name "unconnected-(IC33B-~{Q}-Pad8)") (class "Default")
      (node (ref "IC33") (pin "8") (pinfunction "~{Q}_8") (pintype "output"))
    )
    (net (code "260") (name "unconnected-(IC40A-Q-Pad5)") (class "Default")
      (node (ref "IC40") (pin "5") (pinfunction "Q_5") (pintype "output"))
    )
    (net (code "261") (name "unconnected-(IC40B-Q-Pad9)") (class "Default")
      (node (ref "IC40") (pin "9") (pinfunction "Q_9") (pintype "output"))
    )
    (net (code "262") (name "unconnected-(P3AA-KL-Pad33)") (class "Default")
      (node (ref "P3") (pin "33") (pinfunction "KL_33") (pintype "passive"))
    )
    (net (code "263") (name "unconnected-(RN19-Pad5)") (class "Default")
      (node (ref "RN19") (pin "5") (pinfunction "5_5") (pintype "passive"))
    )
    (net (code "264") (name "unconnected-(RN19-Pad6)") (class "Default")
      (node (ref "RN19") (pin "6") (pinfunction "6_6") (pintype "passive"))
    )
    (net (code "265") (name "unconnected-(XTAL1-TS-Pad1)") (class "Default")
      (node (ref "XTAL1") (pin "1") (pinfunction "TS_1") (pintype "passive"))
    )
    (net (code "266") (name "~{ACCPL}") (class "Default")
      (node (ref "P1") (pin "39") (pinfunction "KL_39") (pintype "passive"))
    )
    (net (code "267") (name "~{AINDEX}") (class "Default")
      (node (ref "P2") (pin "20") (pinfunction "KL_20") (pintype "passive"))
    )
    (net (code "268") (name "~{BUSEN}") (class "Default")
      (node (ref "IC34") (pin "4") (pinfunction "O_4") (pintype "output"))
      (node (ref "IC35") (pin "19") (pinfunction "G_19") (pintype "input"))
      (node (ref "IC36") (pin "19") (pinfunction "G_19") (pintype "input"))
    )
    (net (code "269") (name "~{CLI}") (class "Default")
      (node (ref "IC29") (pin "2") (pinfunction "I1_2") (pintype "input"))
      (node (ref "P1") (pin "17") (pinfunction "KL_17") (pintype "passive"))
    )
    (net (code "270") (name "~{CLL}") (class "Default")
      (node (ref "P1") (pin "1") (pinfunction "KL_1") (pintype "passive"))
    )
    (net (code "271") (name "~{CPL}") (class "Default")
      (node (ref "P1") (pin "2") (pinfunction "KL_2") (pintype "passive"))
    )
    (net (code "272") (name "~{DEC}") (class "Default")
      (node (ref "P1") (pin "40") (pinfunction "KL_40") (pintype "passive"))
    )
    (net (code "273") (name "~{ENDEXT}") (class "Default")
      (node (ref "EXP1") (pin "B7") (pinfunction "7_B7") (pintype "passive"))
    )
    (net (code "274") (name "~{END}") (class "Default")
      (node (ref "IC21") (pin "11") (pinfunction "CLK_11") (pintype "input"))
      (node (ref "IC22") (pin "11") (pinfunction "CLK_11") (pintype "input"))
      (node (ref "P1") (pin "10") (pinfunction "KL_10") (pintype "passive"))
    )
    (net (code "275") (name "~{FINT}") (class "Default")
      (node (ref "IC30") (pin "1") (pinfunction "I0_1") (pintype "input"))
      (node (ref "IC31") (pin "6") (pinfunction "~{Q}_6") (pintype "output"))
    )
    (net (code "276") (name "~{FPRESET}") (class "Default")
      (node (ref "D1") (pin "C") (pinfunction "C_C") (pintype "passive"))
      (node (ref "P3") (pin "28") (pinfunction "KL_28") (pintype "passive"))
    )
    (net (code "277") (name "~{HALT}") (class "Default")
      (node (ref "EXP1") (pin "A19") (pinfunction "19_A19") (pintype "passive"))
      (node (ref "IC28") (pin "2") (pinfunction "I_2") (pintype "input"))
    )
    (net (code "278") (name "~{INCPC}") (class "Default")
      (node (ref "P2") (pin "3") (pinfunction "KL_3") (pintype "passive"))
    )
    (net (code "279") (name "~{IODEV1XX}") (class "Default")
      (node (ref "EXP1") (pin "B24") (pinfunction "24_B24") (pintype "passive"))
    )
    (net (code "280") (name "~{IODEV2XX}") (class "Default")
      (node (ref "EXP1") (pin "B25") (pinfunction "25_B25") (pintype "passive"))
    )
    (net (code "281") (name "~{IODEV3XX}") (class "Default")
      (node (ref "EXP1") (pin "B26") (pinfunction "26_B26") (pintype "passive"))
    )
    (net (code "282") (name "~{IO}") (class "Default")
      (node (ref "EXP1") (pin "C14") (pinfunction "14_C14") (pintype "passive"))
      (node (ref "IC34") (pin "3") (pinfunction "I1_3") (pintype "input"))
    )
    (net (code "283") (name "~{IRQ0}") (class "Default")
      (node (ref "EXP1") (pin "C18") (pinfunction "18_C18") (pintype "passive"))
    )
    (net (code "284") (name "~{IRQ1}") (class "Default")
      (node (ref "EXP1") (pin "C19") (pinfunction "19_C19") (pintype "passive"))
    )
    (net (code "285") (name "~{IRQ2}") (class "Default")
      (node (ref "EXP1") (pin "C20") (pinfunction "20_C20") (pintype "passive"))
    )
    (net (code "286") (name "~{IRQ3}") (class "Default")
      (node (ref "EXP1") (pin "A13") (pinfunction "13_A13") (pintype "passive"))
    )
    (net (code "287") (name "~{IRQ4}") (class "Default")
      (node (ref "EXP1") (pin "A14") (pinfunction "14_A14") (pintype "passive"))
    )
    (net (code "288") (name "~{IRQ5}") (class "Default")
      (node (ref "EXP1") (pin "A15") (pinfunction "15_A15") (pintype "passive"))
    )
    (net (code "289") (name "~{IRQ6}") (class "Default")
      (node (ref "EXP1") (pin "A16") (pinfunction "16_A16") (pintype "passive"))
    )
    (net (code "290") (name "~{IRQ7}") (class "Default")
      (node (ref "EXP1") (pin "A18") (pinfunction "18_A18") (pintype "passive"))
    )
    (net (code "291") (name "~{IRQS}") (class "Default")
      (node (ref "EXP1") (pin "A30") (pinfunction "30_A30") (pintype "passive"))
      (node (ref "IC21") (pin "8") (pinfunction "~{Q}_8") (pintype "output"))
    )
    (net (code "292") (name "~{IRQ}") (class "Default")
      (node (ref "EXP1") (pin "C29") (pinfunction "29_C29") (pintype "passive"))
      (node (ref "IC30") (pin "2") (pinfunction "I1_2") (pintype "input"))
      (node (ref "R48") (pin "1") (pinfunction "1_1") (pintype "passive"))
    )
    (net (code "293") (name "~{MASKEDIRQ}") (class "Default")
      (node (ref "IC30") (pin "4") (pinfunction "O_4") (pintype "output"))
      (node (ref "IC31") (pin "10") (pinfunction "PRE_10") (pintype "input"))
    )
    (net (code "294") (name "~{MEM}") (class "Default")
      (node (ref "EXP1") (pin "C13") (pinfunction "13_C13") (pintype "passive"))
      (node (ref "IC34") (pin "1") (pinfunction "I0_1") (pintype "input"))
    )
    (net (code "295") (name "~{OPIF3}") (class "Default")
      (node (ref "IC17") (pin "4") (pinfunction "O_4") (pintype "output"))
      (node (ref "IC19") (pin "7") (pinfunction "~{OE}_7") (pintype "input"))
    )
    (net (code "296") (name "~{RAC}") (class "Default")
      (node (ref "P2") (pin "4") (pinfunction "KL_4") (pintype "passive"))
    )
    (net (code "297") (name "~{RAGL}") (class "Default")
      (node (ref "IC23") (pin "1") (pinfunction "G1_1") (pintype "input"))
      (node (ref "IC24") (pin "1") (pinfunction "G1_1") (pintype "input"))
      (node (ref "P1") (pin "3") (pinfunction "KL_3") (pintype "passive"))
    )
    (net (code "298") (name "~{RDR}") (class "Default")
      (node (ref "P2") (pin "5") (pinfunction "KL_5") (pintype "passive"))
    )
    (net (code "299") (name "~{RESET_OR_CLI}") (class "Default")
      (node (ref "IC29") (pin "4") (pinfunction "O_4") (pintype "output"))
      (node (ref "IC31") (pin "14") (pinfunction "CLR_14") (pintype "input"))
      (node (ref "IC31") (pin "15") (pinfunction "CLR_15") (pintype "input"))
    )
    (net (code "300") (name "~{RESET}") (class "Default")
      (node (ref "D1") (pin "A") (pinfunction "A_A") (pintype "passive"))
      (node (ref "D2") (pin "A") (pinfunction "A_A") (pintype "passive"))
      (node (ref "D3") (pin "A") (pinfunction "A_A") (pintype "passive"))
      (node (ref "EXP1") (pin "C30") (pinfunction "30_C30") (pintype "passive"))
      (node (ref "IC12") (pin "13") (pinfunction "CLR_13") (pintype "input"))
      (node (ref "IC2") (pin "11") (pinfunction "LOAD_11") (pintype "input"))
      (node (ref "IC21") (pin "13") (pinfunction "CLR_13") (pintype "input"))
      (node (ref "IC21") (pin "4") (pinfunction "PRE_4") (pintype "input"))
      (node (ref "IC29") (pin "1") (pinfunction "I0_1") (pintype "input"))
      (node (ref "IC33") (pin "1") (pinfunction "CLR_1") (pintype "input"))
      (node (ref "IC39") (pin "3") (pinfunction "I1_3") (pintype "input"))
      (node (ref "IC5") (pin "10") (pinfunction "CCLR_10") (pintype "input"))
      (node (ref "R13") (pin "1") (pinfunction "1_1") (pintype "passive"))
    )
    (net (code "301") (name "~{RPC}") (class "Default")
      (node (ref "P2") (pin "6") (pinfunction "KL_6") (pintype "passive"))
    )
    (net (code "302") (name "~{RSTHOLD-SHORT}") (class "Default")
      (node (ref "IC5") (pin "12") (pinfunction "CCKEN_12") (pintype "input"))
      (node (ref "JP2") (pin "10") (pinfunction "10_10") (pintype "passive"))
      (node (ref "JP2") (pin "2") (pinfunction "2_2") (pintype "passive"))
      (node (ref "JP2") (pin "4") (pinfunction "4_4") (pintype "passive"))
      (node (ref "JP2") (pin "6") (pinfunction "6_6") (pintype "passive"))
      (node (ref "JP2") (pin "8") (pinfunction "8_8") (pintype "passive"))
      (node (ref "R14") (pin "2") (pinfunction "2_2") (pintype "passive"))
      (node (ref "R4") (pin "2") (pinfunction "2_2") (pintype "passive"))
    )
    (net (code "303") (name "~{RSTHOLD}") (class "Default")
      (node (ref "EXP1") (pin "B22") (pinfunction "22_B22") (pintype "passive"))
      (node (ref "IC6") (pin "1") (pinfunction "G1_1") (pintype "input"))
      (node (ref "IC6") (pin "19") (pinfunction "G2_19") (pintype "input"))
      (node (ref "IC7") (pin "1") (pinfunction "G1_1") (pintype "input"))
      (node (ref "IC7") (pin "19") (pinfunction "G2_19") (pintype "input"))
      (node (ref "R14") (pin "1") (pinfunction "1_1") (pintype "passive"))
    )
    (net (code "304") (name "~{R}") (class "Default")
      (node (ref "EXP1") (pin "C15") (pinfunction "15_C15") (pintype "passive"))
      (node (ref "IC35") (pin "1") (pinfunction "DIR_1") (pintype "input"))
      (node (ref "IC36") (pin "1") (pinfunction "DIR_1") (pintype "input"))
    )
    (net (code "305") (name "~{SKIP0}") (class "Default")
      (node (ref "IC20") (pin "4") (pinfunction "O_4") (pintype "output"))
      (node (ref "IC21") (pin "2") (pinfunction "D_2") (pintype "input"))
    )
    (net (code "306") (name "~{SKIPEXT}") (class "Default")
      (node (ref "EXP1") (pin "B6") (pinfunction "6_B6") (pintype "passive"))
      (node (ref "IC20") (pin "3") (pinfunction "I1_3") (pintype "input"))
      (node (ref "R40") (pin "2") (pinfunction "2_2") (pintype "passive"))
    )
    (net (code "307") (name "~{SKIP}") (class "Default")
      (node (ref "P1") (pin "15") (pinfunction "KL_15") (pintype "passive"))
      (node (ref "R41") (pin "1") (pinfunction "1_1") (pintype "passive"))
    )
    (net (code "308") (name "~{STI-DELAY}") (class "Default")
      (node (ref "IC12") (pin "1") (pinfunction "CLR_1") (pintype "input"))
      (node (ref "IC12") (pin "6") (pinfunction "~{Q}_6") (pintype "output"))
      (node (ref "IC31") (pin "4") (pinfunction "PRE_4") (pintype "input"))
    )
    (net (code "309") (name "~{STI}") (class "Default")
      (node (ref "IC12") (pin "10") (pinfunction "PRE_10") (pintype "input"))
      (node (ref "P1") (pin "16") (pinfunction "KL_16") (pintype "passive"))
    )
    (net (code "310") (name "~{STPAC}") (class "Default")
      (node (ref "P2") (pin "1") (pinfunction "KL_1") (pintype "passive"))
    )
    (net (code "311") (name "~{STPDR}") (class "Default")
      (node (ref "P2") (pin "2") (pinfunction "KL_2") (pintype "passive"))
    )
    (net (code "312") (name "~{SYSDEV}") (class "Default")
      (node (ref "EXP1") (pin "A28") (pinfunction "28_A28") (pintype "passive"))
    )
    (net (code "313") (name "~{T34}") (class "Default")
      (node (ref "EXP1") (pin "B27") (pinfunction "27_B27") (pintype "passive"))
      (node (ref "IC3") (pin "11") (pinfunction "Y1_11") (pintype "output"))
      (node (ref "IC32") (pin "2") (pinfunction "I1_2") (pintype "input"))
    )
    (net (code "314") (name "~{WAC}") (class "Default")
      (node (ref "P2") (pin "7") (pinfunction "KL_7") (pintype "passive"))
    )
    (net (code "315") (name "~{WAITING}") (class "Default")
      (node (ref "IC33") (pin "6") (pinfunction "~{Q}_6") (pintype "output"))
      (node (ref "IC34") (pin "6") (pinfunction "I2_6") (pintype "input"))
    )
    (net (code "316") (name "~{WALU}") (class "Default")
      (node (ref "P1") (pin "4") (pinfunction "KL_4") (pintype "passive"))
    )
    (net (code "317") (name "~{WAR}") (class "Default")
      (node (ref "P2") (pin "8") (pinfunction "KL_8") (pintype "passive"))
    )
    (net (code "318") (name "~{WCLR}") (class "Default")
      (node (ref "IC37") (pin "1") (pinfunction "I_1") (pintype "input"))
      (node (ref "IC40") (pin "8") (pinfunction "~{Q}_8") (pintype "output"))
      (node (ref "JP3") (pin "1") (pinfunction "1_1") (pintype "passive"))
    )
    (net (code "319") (name "~{WDR}") (class "Default")
      (node (ref "P2") (pin "9") (pinfunction "KL_9") (pintype "passive"))
    )
    (net (code "320") (name "~{WEN}") (class "Default")
      (node (ref "IC38") (pin "6") (pinfunction "I1_6") (pintype "input"))
      (node (ref "P1") (pin "8") (pinfunction "KL_8") (pintype "passive"))
    )
    (net (code "321") (name "~{WIR}") (class "Default")
      (node (ref "IC11") (pin "2") (pinfunction "I_2") (pintype "input"))
      (node (ref "P2") (pin "19") (pinfunction "KL_19") (pintype "passive"))
    )
    (net (code "322") (name "~{WPC}") (class "Default")
      (node (ref "IC12") (pin "11") (pinfunction "CLK_11") (pintype "input"))
      (node (ref "IC12") (pin "3") (pinfunction "CLK_3") (pintype "input"))
      (node (ref "P2") (pin "10") (pinfunction "KL_10") (pintype "passive"))
    )
    (net (code "323") (name "~{WS}") (class "Default")
      (node (ref "EXP1") (pin "B8") (pinfunction "8_B8") (pintype "passive"))
      (node (ref "IC32") (pin "1") (pinfunction "I0_1") (pintype "input"))
    )
    (net (code "324") (name "~{W}") (class "Default")
      (node (ref "EXP1") (pin "C16") (pinfunction "16_C16") (pintype "passive"))
      (node (ref "R51") (pin "1") (pinfunction "1_1") (pintype "passive"))
    )
    (net (code "325") (name "~{[R1]}") (class "Default")
      (node (ref "EXP1") (pin "B9") (pinfunction "9_B9") (pintype "passive"))
    )
    (net (code "326") (name "~{[R6]}") (class "Default")
      (node (ref "EXP1") (pin "B10") (pinfunction "10_B10") (pintype "passive"))
    )
    (net (code "327") (name "~{[R7]}") (class "Default")
      (node (ref "EXP1") (pin "B11") (pinfunction "11_B11") (pintype "passive"))
    )
    (net (code "328") (name "~{[W1]}") (class "Default")
      (node (ref "EXP1") (pin "B12") (pinfunction "12_B12") (pintype "passive"))
    )
    (net (code "329") (name "÷2") (class "Default")
      (node (ref "IC2") (pin "3") (pinfunction "QA_3") (pintype "output"))
      (node (ref "IC3") (pin "2") (pinfunction "A_2") (pintype "input"))
    )
    (net (code "330") (name "÷4") (class "Default")
      (node (ref "IC2") (pin "2") (pinfunction "QB_2") (pintype "output"))
      (node (ref "IC3") (pin "14") (pinfunction "A_14") (pintype "input"))
      (node (ref "IC3") (pin "3") (pinfunction "B_3") (pintype "input"))
    )
  )
)
